# MainControl20V05.net
KiCad netlist of a schematic drawn in Altium Designer
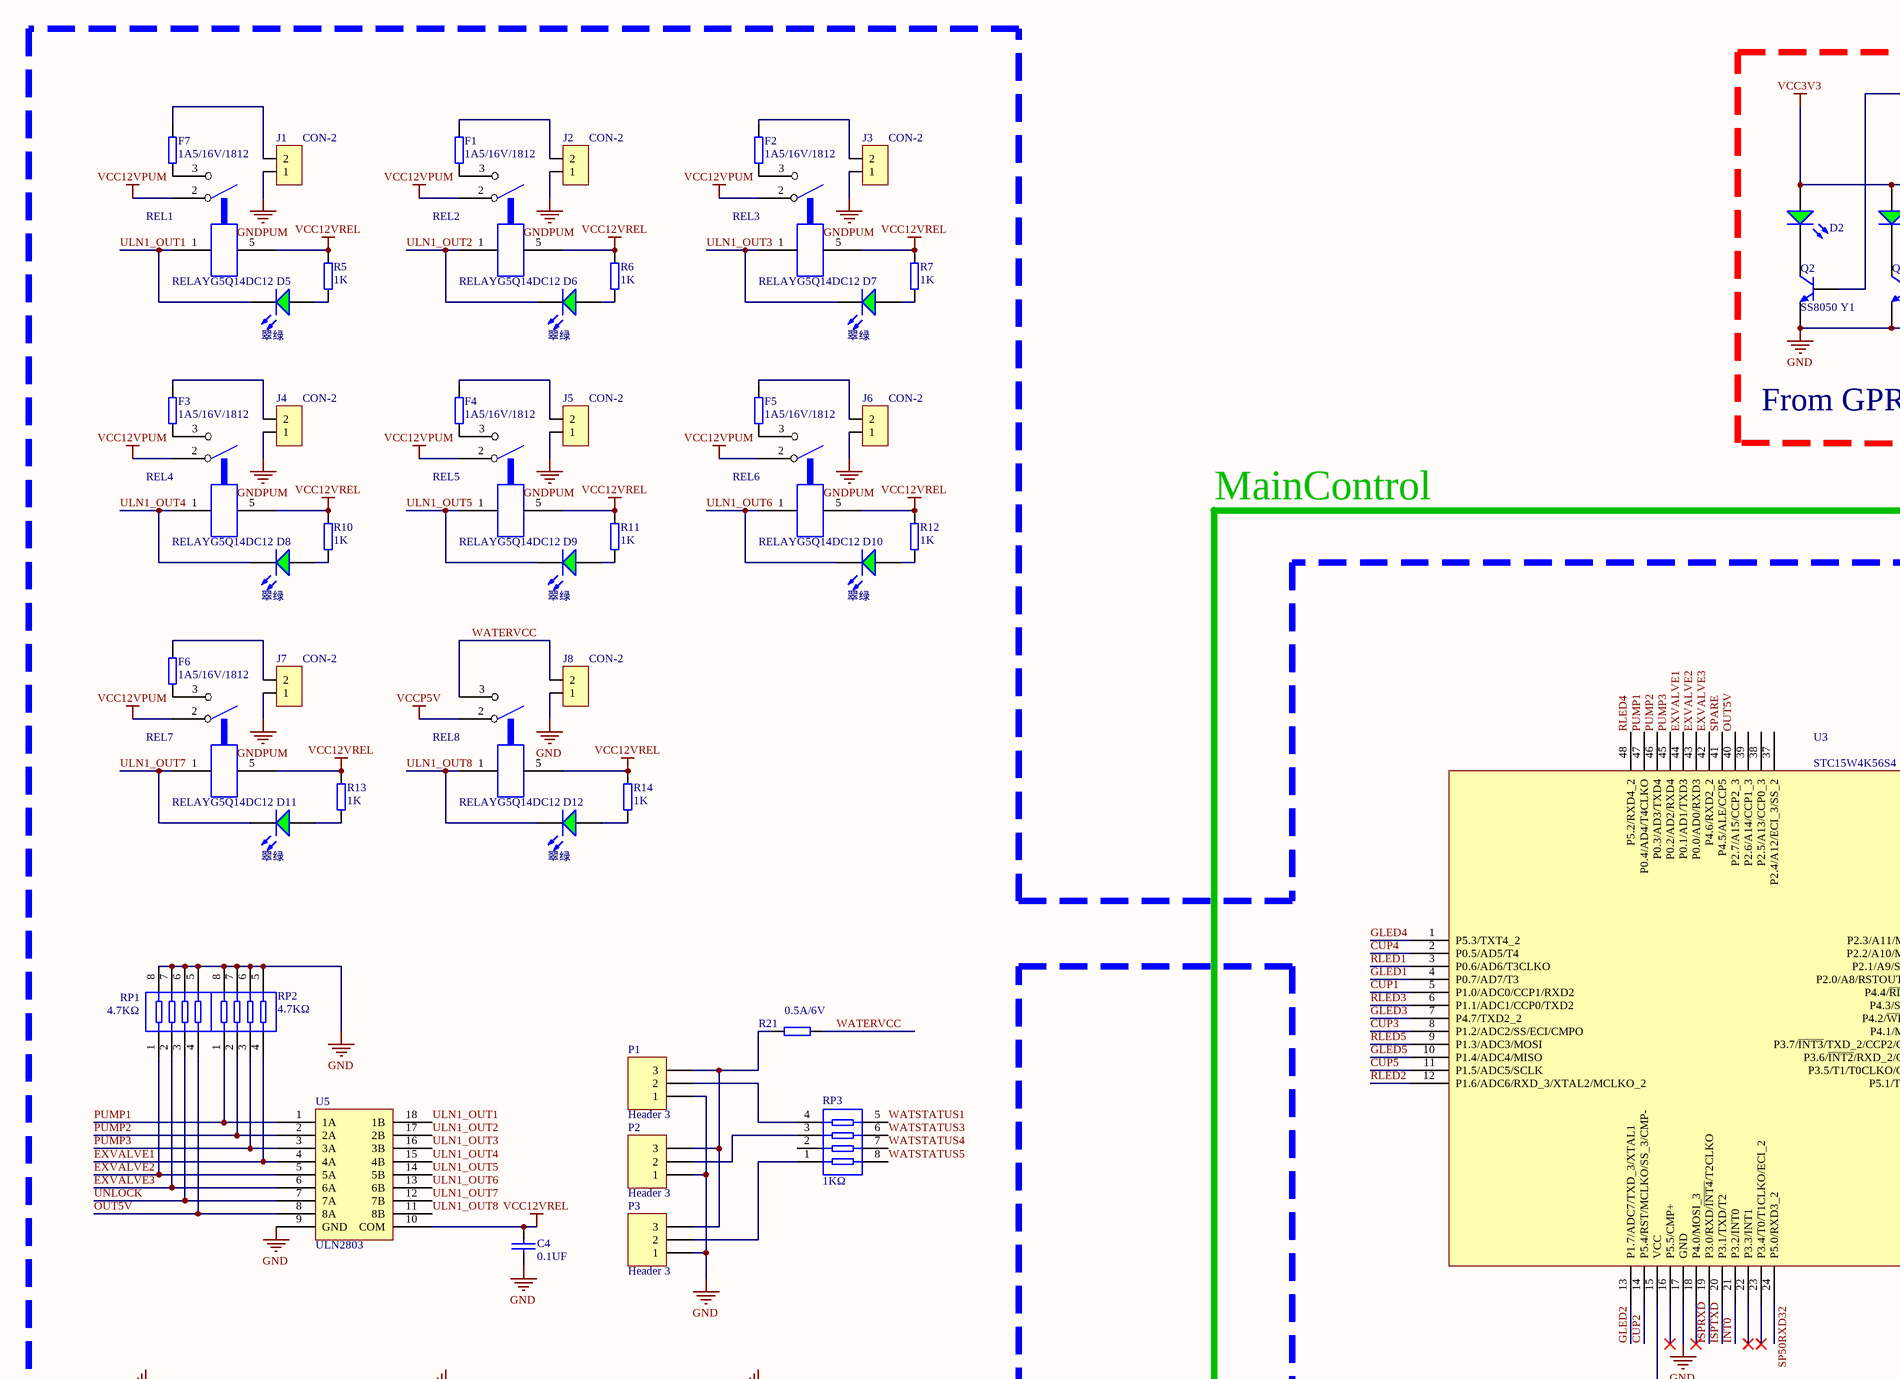
[diagram p0: MainControl20V05.SchDoc, top left]
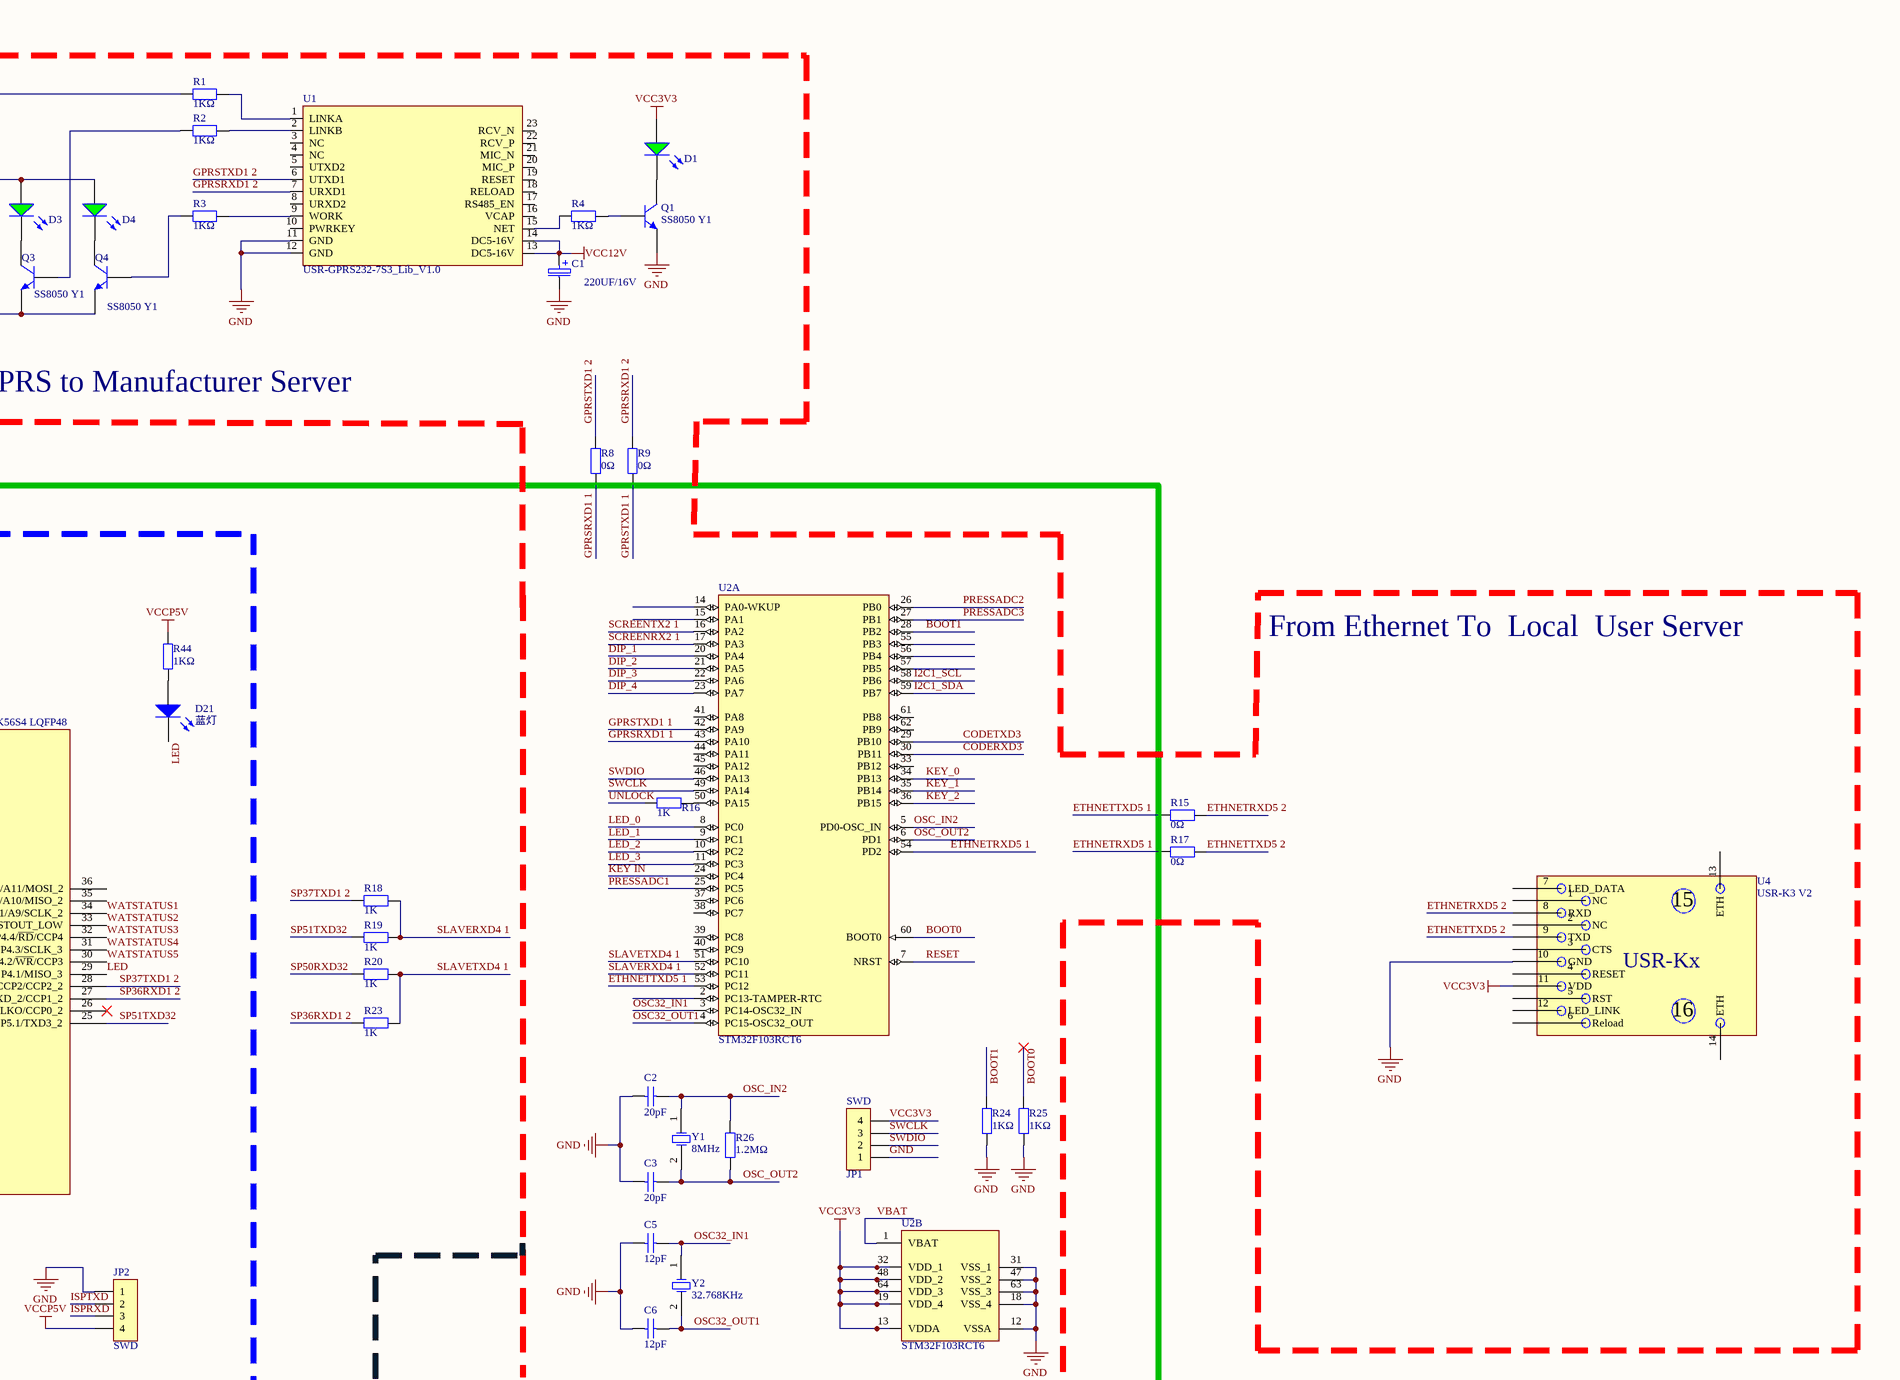
[diagram p1: MainControl20V05.SchDoc, top right]
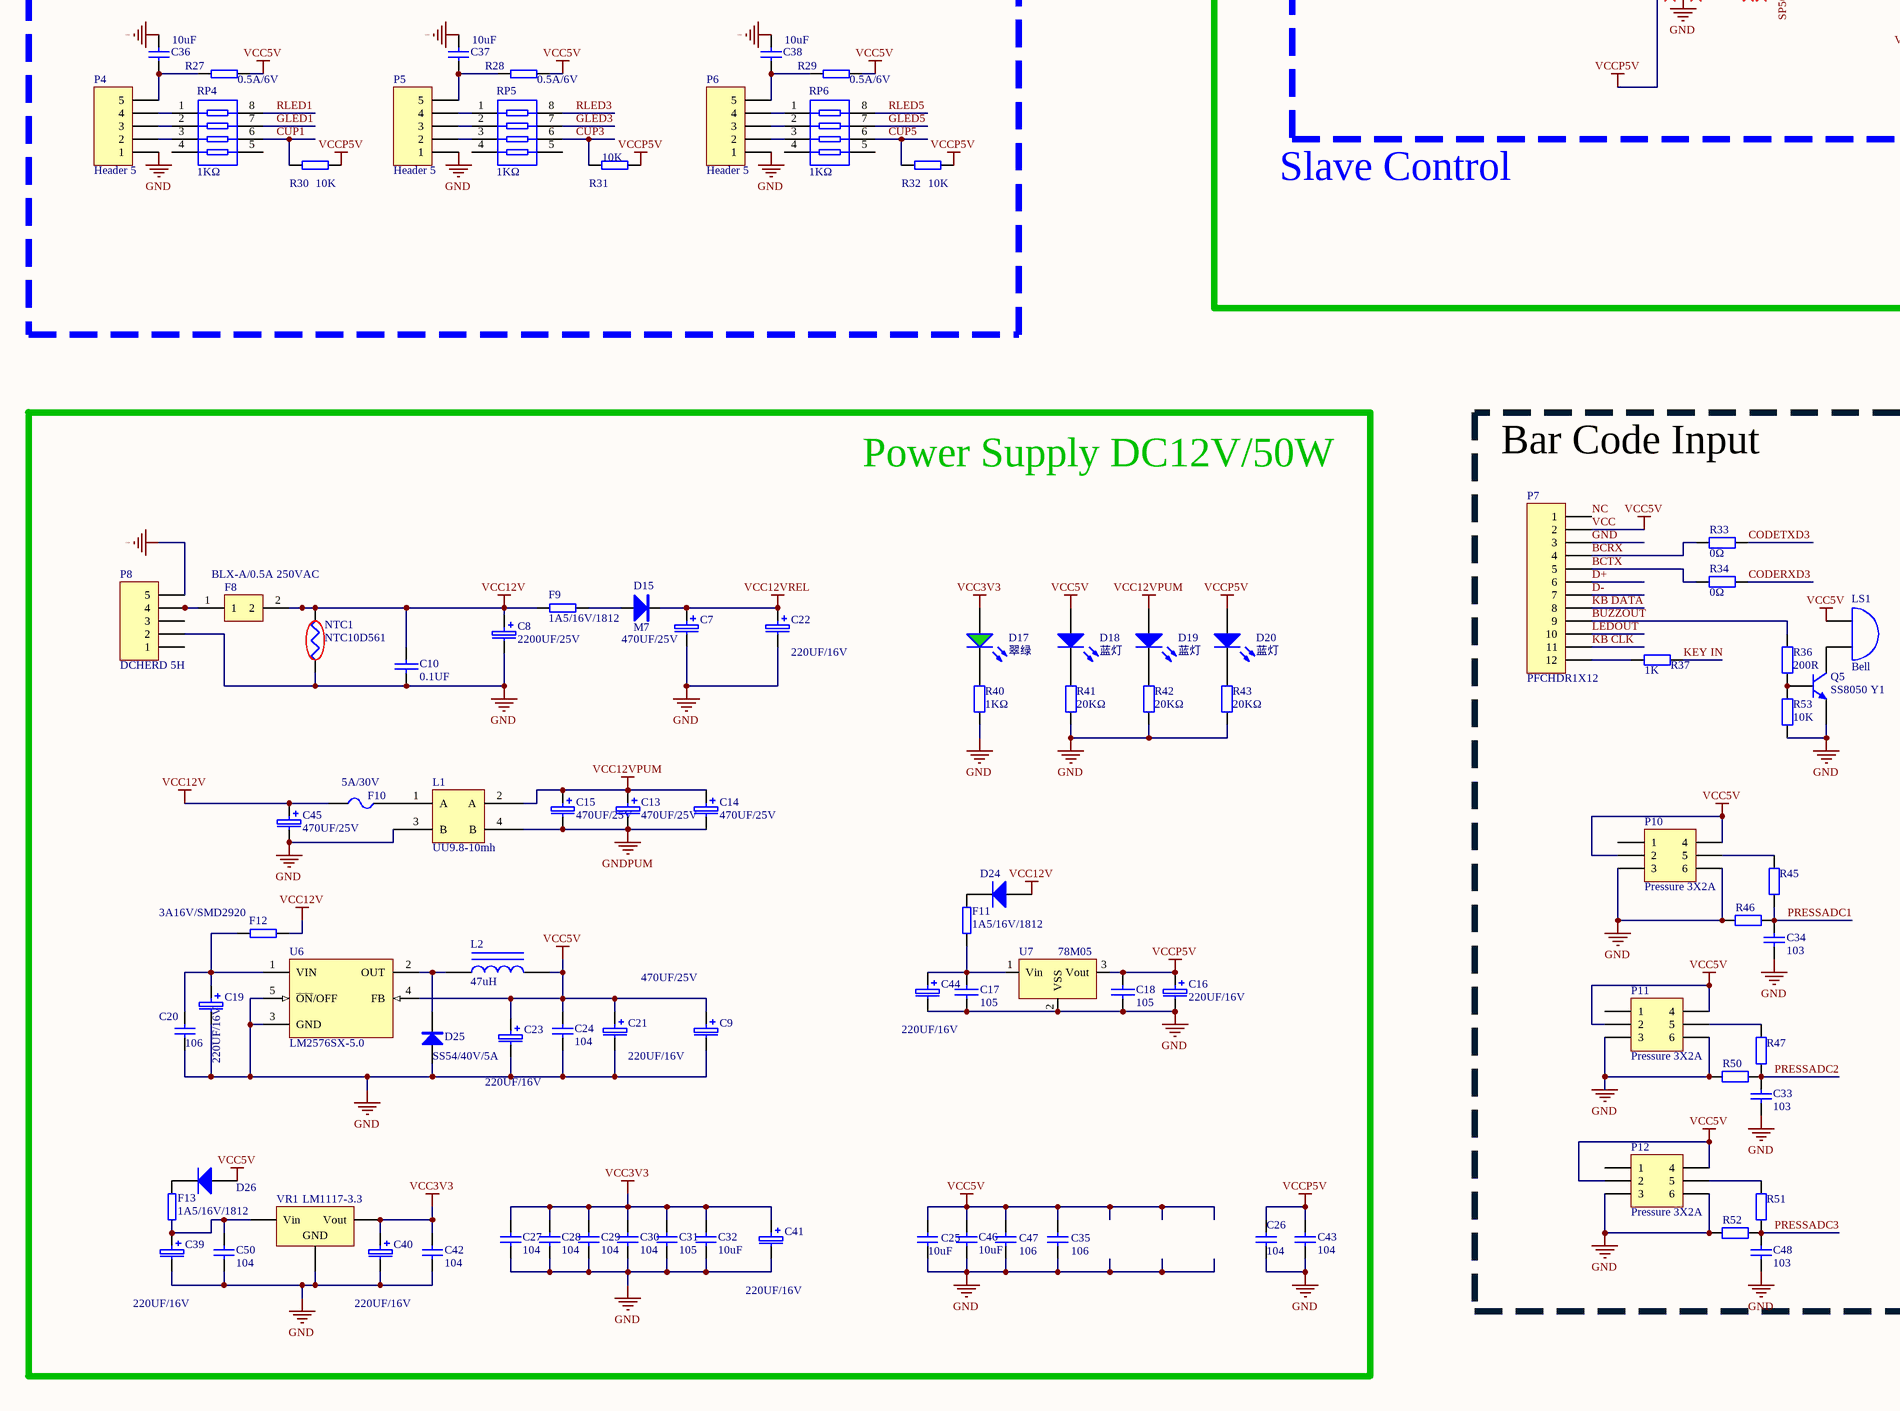
[diagram p2: MainControl20V05.SchDoc, bottom left]
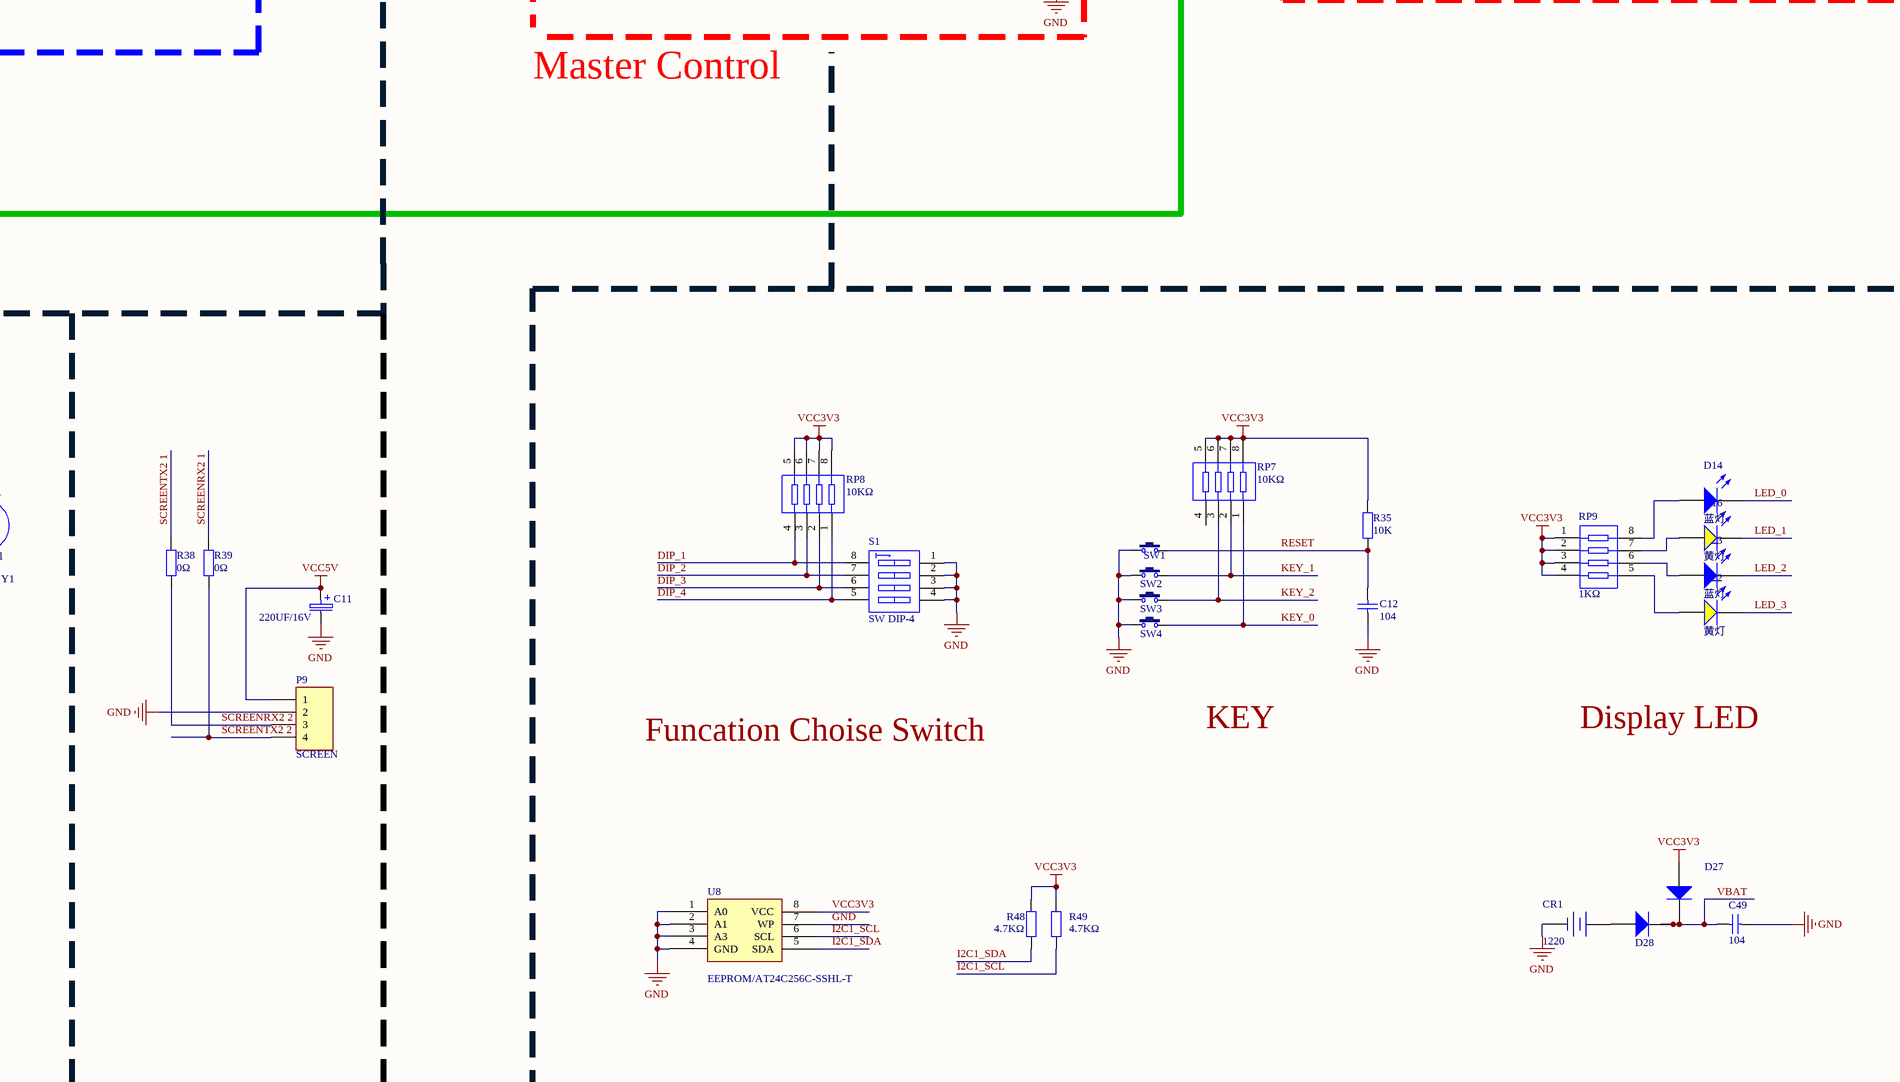
[diagram p3: MainControl20V05.SchDoc, bottom right]

(export (version "E")
  (design (tool "Eeschema 10.0.6"))
  (components
    (comp (ref "C1")
      (value "220UF/16V")
      (footprint "6SMD-ECAP-6.3X7.7")
      (libsource (lib "WegeV1") (part "EC"))
    )
    (comp (ref "C2")
      (value "20pF")
      (footprint "0805_C")
      (description "贴片电容")
      (libsource (lib "Cap") (part "1206 470pF (471) 10% 50V"))
    )
    (comp (ref "C3")
      (value "20pF")
      (footprint "0805_C")
      (description "贴片电容")
      (libsource (lib "Cap") (part "1206 470pF (471) 10% 50V"))
    )
    (comp (ref "C4")
      (value "0.1UF")
      (footprint "0805_C")
      (description "Cap")
      (libsource (lib "RX9910") (part "CAP-SMD"))
    )
    (comp (ref "C5")
      (value "12pF")
      (footprint "0805_C")
      (description "贴片电容")
      (libsource (lib "Cap") (part "1206 470pF (471) 10% 50V"))
    )
    (comp (ref "C6")
      (value "12pF")
      (footprint "0805_C")
      (description "贴片电容")
      (libsource (lib "Cap") (part "1206 470pF (471) 10% 50V"))
    )
    (comp (ref "C7") (value "470UF/25V") (footprint "C1020") (libsource (lib "WegeV1") (part "EC")))
    (comp (ref "C8") (value "2200UF/25V") (footprint "C3618") (libsource (lib "WegeV1") (part "EC")))
    (comp (ref "C9") (value "470UF/25V") (footprint "C1020") (libsource (lib "WegeV1") (part "EC")))
    (comp (ref "C10")
      (value "0.1UF")
      (footprint "0805_C")
      (description "安规电容 X2 275V 0.1uF 100nF 104K 脚距10mm")
      (libsource (lib "WegeV1") (part "CAP-X"))
    )
    (comp (ref "C11")
      (value "220UF/16V")
      (footprint "6SMD-ECAP-6.3X7.7")
      (libsource (lib "WegeV1") (part "EC"))
    )
    (comp (ref "C12")
      (value "104")
      (footprint "0805_C")
      (description "贴片电容")
      (libsource (lib "Cap") (part "1206 100nF (104) 10% 50V"))
    )
    (comp (ref "C13") (value "470UF/25V") (footprint "C1020") (libsource (lib "WegeV1") (part "EC")))
    (comp (ref "C14") (value "470UF/25V") (footprint "C1020") (libsource (lib "WegeV1") (part "EC")))
    (comp (ref "C15") (value "470UF/25V") (footprint "C1020") (libsource (lib "WegeV1") (part "EC")))
    (comp (ref "C16")
      (value "220UF/16V")
      (footprint "6SMD-ECAP-6.3X7.7")
      (libsource (lib "WegeV1") (part "EC"))
    )
    (comp (ref "C17")
      (value "105")
      (footprint "0805_C")
      (description "Cap")
      (libsource (lib "RX9910") (part "CAP-SMD"))
    )
    (comp (ref "C18")
      (value "105")
      (footprint "0805_C")
      (description "Cap")
      (libsource (lib "RX9910") (part "CAP-SMD"))
    )
    (comp (ref "C19")
      (value "220UF/16V")
      (footprint "6SMD-ECAP-6.3X7.7")
      (libsource (lib "WegeV1") (part "EC"))
    )
    (comp (ref "C20")
      (value "106")
      (footprint "1206_R")
      (description "贴片电容")
      (libsource (lib "Cap") (part "1206 10uF (106) 10% 50V"))
    )
    (comp (ref "C21")
      (value "220UF/16V")
      (footprint "6SMD-ECAP-6.3X7.7")
      (libsource (lib "WegeV1") (part "EC"))
    )
    (comp (ref "C22")
      (value "220UF/16V")
      (footprint "6SMD-ECAP-6.3X7.7")
      (libsource (lib "WegeV1") (part "EC"))
    )
    (comp (ref "C23")
      (value "220UF/16V")
      (footprint "6SMD-ECAP-6.3X7.7")
      (libsource (lib "WegeV1") (part "EC"))
    )
    (comp (ref "C24")
      (value "104")
      (footprint "0805_C")
      (description "贴片电容")
      (libsource (lib "Cap") (part "1206 220nF (224) 10% 50V"))
    )
    (comp (ref "C25")
      (value "10uF")
      (footprint "0805_C")
      (description "贴片电容")
      (libsource (lib "Cap") (part "1206 100nF (104) 10% 50V"))
    )
    (comp (ref "C26")
      (value "104")
      (footprint "0805_C")
      (description "贴片电容")
      (libsource (lib "Cap") (part "1206 100nF (104) 10% 50V"))
    )
    (comp (ref "C27")
      (value "104")
      (footprint "0805_C")
      (description "贴片电容")
      (libsource (lib "Cap") (part "1206 100nF (104) 10% 50V"))
    )
    (comp (ref "C28")
      (value "104")
      (footprint "0805_C")
      (description "贴片电容")
      (libsource (lib "Cap") (part "1206 100nF (104) 10% 50V"))
    )
    (comp (ref "C29")
      (value "104")
      (footprint "0805_C")
      (description "贴片电容")
      (libsource (lib "Cap") (part "1206 100nF (104) 10% 50V"))
    )
    (comp (ref "C30")
      (value "104")
      (footprint "0805_C")
      (description "贴片电容")
      (libsource (lib "Cap") (part "1206 100nF (104) 10% 50V"))
    )
    (comp (ref "C31")
      (value "105")
      (footprint "0805_C")
      (description "贴片电容")
      (libsource (lib "Cap") (part "1206 100nF (104) 10% 50V"))
    )
    (comp (ref "C32")
      (value "10uF")
      (footprint "0805_C")
      (description "贴片电容")
      (libsource (lib "Cap") (part "1206 100nF (104) 10% 50V"))
    )
    (comp (ref "C33")
      (value "103")
      (footprint "0805_C")
      (description "贴片电容")
      (libsource (lib "Cap") (part "1206 100nF (104) 10% 50V"))
    )
    (comp (ref "C34")
      (value "103")
      (footprint "0805_C")
      (description "贴片电容")
      (libsource (lib "Cap") (part "1206 100nF (104) 10% 50V"))
    )
    (comp (ref "C35")
      (value "106")
      (footprint "0805_C")
      (description "贴片电容")
      (libsource (lib "Cap") (part "1206 10uF (106) 10% 50V"))
    )
    (comp (ref "C36")
      (value "10uF")
      (footprint "0805_C")
      (description "贴片电容")
      (libsource (lib "Cap") (part "1206 100nF (104) 10% 50V"))
    )
    (comp (ref "C37")
      (value "10uF")
      (footprint "0805_C")
      (description "贴片电容")
      (libsource (lib "Cap") (part "1206 100nF (104) 10% 50V"))
    )
    (comp (ref "C38")
      (value "10uF")
      (footprint "0805_C")
      (description "贴片电容")
      (libsource (lib "Cap") (part "1206 100nF (104) 10% 50V"))
    )
    (comp (ref "C39")
      (value "220UF/16V")
      (footprint "6SMD-ECAP-6.3X7.7")
      (libsource (lib "WegeV1") (part "EC"))
    )
    (comp (ref "C40")
      (value "220UF/16V")
      (footprint "6SMD-ECAP-6.3X7.7")
      (libsource (lib "WegeV1") (part "EC"))
    )
    (comp (ref "C41")
      (value "220UF/16V")
      (footprint "6SMD-ECAP-6.3X7.7")
      (libsource (lib "WegeV1") (part "EC"))
    )
    (comp (ref "C42")
      (value "104")
      (footprint "0805_C")
      (description "贴片电容")
      (libsource (lib "Cap") (part "1206 100nF (104) 10% 50V"))
    )
    (comp (ref "C43")
      (value "104")
      (footprint "0805_C")
      (description "贴片电容")
      (libsource (lib "Cap") (part "1206 100nF (104) 10% 50V"))
    )
    (comp (ref "C44")
      (value "220UF/16V")
      (footprint "6SMD-ECAP-6.3X7.7")
      (libsource (lib "WegeV1") (part "EC"))
    )
    (comp (ref "C45") (value "470UF/25V") (footprint "C1020") (libsource (lib "WegeV1") (part "EC")))
    (comp (ref "C46")
      (value "10uF")
      (footprint "0805_C")
      (description "贴片电容")
      (libsource (lib "Cap") (part "1206 100nF (104) 10% 50V"))
    )
    (comp (ref "C47")
      (value "106")
      (description "贴片电容")
      (libsource (lib "Cap") (part "1206 10uF (106) 10% 50V"))
    )
    (comp (ref "C48")
      (value "103")
      (footprint "0805_C")
      (description "贴片电容")
      (libsource (lib "Cap") (part "1206 100nF (104) 10% 50V"))
    )
    (comp (ref "C49")
      (value "104")
      (footprint "0805_C")
      (description "贴片电容")
      (libsource (lib "Cap") (part "1206 100nF (104) 10% 50V"))
    )
    (comp (ref "C50")
      (value "104")
      (footprint "0805_C")
      (description "贴片电容")
      (libsource (lib "Cap") (part "1206 100nF (104) 10% 50V"))
    )
    (comp (ref "CR1")
      (value "1220")
      (footprint "CR1220_A")
      (description "微型电池")
      (fields (field (name "版权归属") "源创客"))
      (libsource (lib "15.1 - 未分类器件") (part "CR-3V"))
    )
    (comp (ref "D1")
      (value "翠绿")
      (footprint "0805_LED_S1")
      (description "发光二极管")
      (libsource (lib "LED") (part "0805 翠绿"))
    )
    (comp (ref "D2")
      (value "翠绿")
      (footprint "0805_LED_S1")
      (description "发光二极管")
      (libsource (lib "LED") (part "0805 翠绿"))
    )
    (comp (ref "D3")
      (value "翠绿")
      (footprint "0805_LED_S1")
      (description "发光二极管")
      (libsource (lib "LED") (part "0805 翠绿"))
    )
    (comp (ref "D4")
      (value "翠绿")
      (footprint "0805_LED_S1")
      (description "发光二极管")
      (libsource (lib "LED") (part "0805 翠绿"))
    )
    (comp (ref "D5")
      (value "翠绿")
      (footprint "0805_LED_S1")
      (description "发光二极管")
      (libsource (lib "LED") (part "0805 翠绿"))
    )
    (comp (ref "D6")
      (value "翠绿")
      (footprint "0805_LED_S1")
      (description "发光二极管")
      (libsource (lib "LED") (part "0805 翠绿"))
    )
    (comp (ref "D7")
      (value "翠绿")
      (footprint "0805_LED_S1")
      (description "发光二极管")
      (libsource (lib "LED") (part "0805 翠绿"))
    )
    (comp (ref "D8")
      (value "翠绿")
      (footprint "0805_LED_S1")
      (description "发光二极管")
      (libsource (lib "LED") (part "0805 翠绿"))
    )
    (comp (ref "D9")
      (value "翠绿")
      (footprint "0805_LED_S1")
      (description "发光二极管")
      (libsource (lib "LED") (part "0805 翠绿"))
    )
    (comp (ref "D10")
      (value "翠绿")
      (footprint "0805_LED_S1")
      (description "发光二极管")
      (libsource (lib "LED") (part "0805 翠绿"))
    )
    (comp (ref "D11")
      (value "翠绿")
      (footprint "0805_LED_S1")
      (description "发光二极管")
      (libsource (lib "LED") (part "0805 翠绿"))
    )
    (comp (ref "D12")
      (value "翠绿")
      (footprint "0805_LED_S1")
      (description "发光二极管")
      (libsource (lib "LED") (part "0805 翠绿"))
    )
    (comp (ref "D14")
      (value "蓝灯")
      (footprint "0805_LED_S1")
      (description "发光二极管")
      (libsource (lib "LED") (part "0805 蓝灯"))
    )
    (comp (ref "D15") (value "M7") (footprint "DO-41") (libsource (lib "WegeV1") (part "M7")))
    (comp (ref "D16")
      (value "黄灯")
      (footprint "0805_LED_S1")
      (description "发光二极管")
      (libsource (lib "LED") (part "0805 黄灯"))
    )
    (comp (ref "D17")
      (value "翠绿")
      (footprint "0805_LED_S1")
      (description "发光二极管")
      (libsource (lib "LED") (part "0805 翠绿"))
    )
    (comp (ref "D18")
      (value "蓝灯")
      (footprint "0805_LED_S1")
      (description "发光二极管")
      (libsource (lib "LED") (part "0805 蓝灯"))
    )
    (comp (ref "D19")
      (value "蓝灯")
      (footprint "0805_LED_S1")
      (description "发光二极管")
      (libsource (lib "LED") (part "0805 蓝灯"))
    )
    (comp (ref "D20")
      (value "蓝灯")
      (footprint "0805_LED_S1")
      (description "发光二极管")
      (libsource (lib "LED") (part "0805 蓝灯"))
    )
    (comp (ref "D21")
      (value "蓝灯")
      (footprint "0805_LED_S1")
      (description "发光二极管")
      (libsource (lib "LED") (part "0805 蓝灯"))
    )
    (comp (ref "D22")
      (value "黄灯")
      (footprint "0805_LED_S1")
      (description "发光二极管")
      (libsource (lib "LED") (part "0805 黄灯"))
    )
    (comp (ref "D23")
      (value "蓝灯")
      (footprint "0805_LED_S1")
      (description "发光二极管")
      (libsource (lib "LED") (part "0805 蓝灯"))
    )
    (comp (ref "D24")
      (value "LL4148 LL-34 1206")
      (footprint "LL-34")
      (description "开关二极管")
      (libsource (lib "Diode") (part "LL-34 LL4148 LL-34 1206"))
    )
    (comp (ref "D25")
      (value "SS54/40V/5A")
      (footprint "SMC(DO-214AB)_S1")
      (description "肖特基二极管")
      (fields (field (name "版权归属") "源创客"))
      (libsource (lib "8.1   - 二极管-整流桥") (part "1N5819"))
    )
    (comp (ref "D26")
      (value "LL4148 LL-34 1206")
      (footprint "LL-34")
      (description "开关二极管")
      (libsource (lib "Diode") (part "LL-34 LL4148 LL-34 1206"))
    )
    (comp (ref "D27")
      (value "LL4148 LL-34 1206")
      (footprint "LL-34")
      (description "开关二极管")
      (libsource (lib "Diode") (part "LL-34 LL4148 LL-34 1206"))
    )
    (comp (ref "D28")
      (value "LL4148 LL-34 1206")
      (footprint "LL-34")
      (description "开关二极管")
      (libsource (lib "Diode") (part "LL-34 LL4148 LL-34 1206"))
    )
    (comp (ref "F1")
      (value "1A5/16V/1812")
      (footprint "1812_R")
      (description "SMD")
      (libsource (lib "RX9910") (part "RES-SMD"))
    )
    (comp (ref "F2")
      (value "1A5/16V/1812")
      (footprint "1812_R")
      (description "SMD")
      (libsource (lib "RX9910") (part "RES-SMD"))
    )
    (comp (ref "F3")
      (value "1A5/16V/1812")
      (footprint "1812_R")
      (description "SMD")
      (libsource (lib "RX9910") (part "RES-SMD"))
    )
    (comp (ref "F4")
      (value "1A5/16V/1812")
      (footprint "1812_R")
      (description "SMD")
      (libsource (lib "RX9910") (part "RES-SMD"))
    )
    (comp (ref "F5")
      (value "1A5/16V/1812")
      (footprint "1812_R")
      (description "SMD")
      (libsource (lib "RX9910") (part "RES-SMD"))
    )
    (comp (ref "F6")
      (value "1A5/16V/1812")
      (footprint "1812_R")
      (description "SMD")
      (libsource (lib "RX9910") (part "RES-SMD"))
    )
    (comp (ref "F7")
      (value "1A5/16V/1812")
      (footprint "1812_R")
      (description "SMD")
      (libsource (lib "RX9910") (part "RES-SMD"))
    )
    (comp (ref "F8")
      (value "BLX-A/0.5A 250VAC")
      (footprint "RL30-500")
      (libsource (lib "WegeV1") (part "BLX-A"))
    )
    (comp (ref "F9")
      (value "1A5/16V/1812")
      (footprint "1812_R")
      (description "SMD")
      (libsource (lib "RX9910") (part "RES-SMD"))
    )
    (comp (ref "F10")
      (value "5A/30V")
      (footprint "RL30-500")
      (description "贴片保险丝")
      (fields (field (name "版权归属") "源创客"))
      (libsource (lib "10.1 - 保险丝-晶振") (part "FU"))
    )
    (comp (ref "F11")
      (value "1A5/16V/1812")
      (footprint "1812_R")
      (description "SMD")
      (libsource (lib "RX9910") (part "RES-SMD"))
    )
    (comp (ref "F12")
      (value "3A16V/SMD2920")
      (footprint "SMD2920")
      (description "SMD")
      (libsource (lib "RX9910") (part "RES-SMD"))
    )
    (comp (ref "F13")
      (value "1A5/16V/1812")
      (footprint "1812_R")
      (description "SMD")
      (libsource (lib "RX9910") (part "RES-SMD"))
    )
    (comp (ref "J1") (value "CON-2") (footprint "F396P2-1") (libsource (lib "WegeV1") (part "CON-2")))
    (comp (ref "J2") (value "CON-2") (footprint "F396P2-1") (libsource (lib "WegeV1") (part "CON-2")))
    (comp (ref "J3") (value "CON-2") (footprint "F396P2-1") (libsource (lib "WegeV1") (part "CON-2")))
    (comp (ref "J4") (value "CON-2") (footprint "F396P2-1") (libsource (lib "WegeV1") (part "CON-2")))
    (comp (ref "J5") (value "CON-2") (footprint "F396P2-1") (libsource (lib "WegeV1") (part "CON-2")))
    (comp (ref "J6") (value "CON-2") (footprint "F396P2-1") (libsource (lib "WegeV1") (part "CON-2")))
    (comp (ref "J7") (value "CON-2") (footprint "F396P2-1") (libsource (lib "WegeV1") (part "CON-2")))
    (comp (ref "J8") (value "CON-2") (footprint "F396P2-1") (libsource (lib "WegeV1") (part "CON-2")))
    (comp (ref "JP1")
      (value "SWD")
      (footprint "HDR2.54-M-LI-4P")
      (description "4P接插件")
      (fields (field (name "版权归属") "源创客"))
      (libsource (lib "") (part "Header 4_1"))
    )
    (comp (ref "JP2")
      (value "SWD")
      (footprint "HDR2.54-M-LI-4P")
      (description "4P接插件")
      (fields (field (name "版权归属") "源创客"))
      (libsource (lib "4.5   - 接插件-脚距2.54") (part "Header 4"))
    )
    (comp (ref "L1") (value "UU9.8-10mh") (footprint "TRANS") (libsource (lib "WegeV1") (part "INL-9.8MM")))
    (comp (ref "L2")
      (value "47uH")
      (footprint "H4.7UH")
      (description "贴片电感")
      (libsource (lib "IUD") (part "1206 10uH 10%"))
    )
    (comp (ref "LS1")
      (value "Bell")
      (footprint "BUZZ")
      (description "Electrical Bell")
      (fields (field (name "PUBLISHER") "Altium Limited"))
      (libsource (lib "Miscellaneous Devices") (part "Bell"))
    )
    (comp (ref "NTC1") (value "NTC10D561") (footprint "NTC-10D") (libsource (lib "WegeV1") (part "NTC")))
    (comp (ref "P1")
      (value "Header 3")
      (footprint "XHB3")
      (description "Header, 3-Pin")
      (fields (field (name "PUBLISHER") "Altium Limited"))
      (libsource (lib "Miscellaneous Connectors") (part "Header 3"))
    )
    (comp (ref "P2")
      (value "Header 3")
      (footprint "XHB3")
      (description "Header, 3-Pin")
      (fields (field (name "PUBLISHER") "Altium Limited"))
      (libsource (lib "Miscellaneous Connectors") (part "Header 3"))
    )
    (comp (ref "P3")
      (value "Header 3")
      (footprint "XHB3")
      (description "Header, 3-Pin")
      (fields (field (name "PUBLISHER") "Altium Limited"))
      (libsource (lib "Miscellaneous Connectors") (part "Header 3"))
    )
    (comp (ref "P4")
      (value "Header 5")
      (footprint "XHB5")
      (description "Header, 5-Pin")
      (fields (field (name "PUBLISHER") "Altium Limited"))
      (libsource (lib "Miscellaneous Connectors") (part "Header 5"))
    )
    (comp (ref "P5")
      (value "Header 5")
      (footprint "XHB5")
      (description "Header, 5-Pin")
      (fields (field (name "PUBLISHER") "Altium Limited"))
      (libsource (lib "Miscellaneous Connectors") (part "Header 5"))
    )
    (comp (ref "P6")
      (value "Header 5")
      (footprint "XHB5")
      (description "Header, 5-Pin")
      (fields (field (name "PUBLISHER") "Altium Limited"))
      (libsource (lib "Miscellaneous Connectors") (part "Header 5"))
    )
    (comp (ref "P7")
      (value "PFCHDR1X12")
      (footprint "FPC12/0.5")
      (description "Header, 12-Pin")
      (fields (field (name "PUBLISHER") "Altium Limited"))
      (libsource (lib "Miscellaneous Connectors") (part "MHDR1X12"))
    )
    (comp (ref "P8")
      (value "DCHERD 5H")
      (footprint "DCCON")
      (description "Header, 5-Pin, Right Angle")
      (fields (field (name "PUBLISHER") "Altium Limited"))
      (libsource (lib "Miscellaneous Connectors") (part "Header 5H"))
    )
    (comp (ref "P9")
      (value "SCREEN")
      (footprint "MHDR1X4")
      (description "Header, 4-Pin")
      (fields (field (name "PUBLISHER") "Altium Limited"))
      (libsource (lib "Miscellaneous Connectors") (part "MHDR1X4"))
    )
    (comp (ref "P10")
      (value "Pressure 3X2A")
      (footprint "PRESS")
      (description "Header, 3-Pin, Dual row")
      (fields (field (name "PUBLISHER") "Altium Limited"))
      (libsource (lib "Miscellaneous Connectors") (part "Header 3X2A"))
    )
    (comp (ref "P11")
      (value "Pressure 3X2A")
      (footprint "PRESS")
      (description "Header, 3-Pin, Dual row")
      (fields (field (name "PUBLISHER") "Altium Limited"))
      (libsource (lib "Miscellaneous Connectors") (part "Header 3X2A"))
    )
    (comp (ref "P12")
      (value "Pressure 3X2A")
      (footprint "PRESS")
      (description "Header, 3-Pin, Dual row")
      (fields (field (name "PUBLISHER") "Altium Limited"))
      (libsource (lib "Miscellaneous Connectors") (part "Header 3X2A"))
    )
    (comp (ref "Q1")
      (value "SS8050 Y1")
      (footprint "SOT-23(SOT-23-3)")
      (description "三极管")
      (libsource (lib "Transistor_NPN") (part "SOT-23 SS8050 Y1"))
    )
    (comp (ref "Q2")
      (value "SS8050 Y1")
      (footprint "SOT-23(SOT-23-3)")
      (description "三极管")
      (libsource (lib "Transistor_NPN") (part "SOT-23 SS8050 Y1"))
    )
    (comp (ref "Q3")
      (value "SS8050 Y1")
      (footprint "SOT-23(SOT-23-3)")
      (description "三极管")
      (libsource (lib "Transistor_NPN") (part "SOT-23 SS8050 Y1"))
    )
    (comp (ref "Q4")
      (value "SS8050 Y1")
      (footprint "SOT-23(SOT-23-3)")
      (description "三极管")
      (libsource (lib "Transistor_NPN") (part "SOT-23 SS8050 Y1"))
    )
    (comp (ref "Q5")
      (value "SS8050 Y1")
      (footprint "SOT-23(SOT-23-3)")
      (description "三极管")
      (libsource (lib "Transistor_NPN") (part "SOT-23 SS8050 Y1"))
    )
    (comp (ref "R1")
      (value "1KΩ")
      (footprint "0805_R")
      (description "贴片电阻")
      (libsource (lib "") (part "1206 1KΩ (1001) 1%_2"))
    )
    (comp (ref "R2")
      (value "1KΩ")
      (footprint "0805_R")
      (description "贴片电阻")
      (libsource (lib "") (part "1206 1KΩ (1001) 1%_2"))
    )
    (comp (ref "R3")
      (value "1KΩ")
      (footprint "0805_R")
      (description "贴片电阻")
      (libsource (lib "") (part "1206 1KΩ (1001) 1%_2"))
    )
    (comp (ref "R4")
      (value "1KΩ")
      (footprint "0805_R")
      (description "贴片电阻")
      (libsource (lib "") (part "1206 1KΩ (1001) 1%_3"))
    )
    (comp (ref "R5") (value "1K") (footprint "0805_R") (libsource (lib "WegeV1") (part "RES")))
    (comp (ref "R6") (value "1K") (footprint "0805_R") (libsource (lib "WegeV1") (part "RES")))
    (comp (ref "R7") (value "1K") (footprint "0805_R") (libsource (lib "WegeV1") (part "RES")))
    (comp (ref "R8")
      (value "0Ω")
      (footprint "0805_R")
      (description "贴片电阻")
      (libsource (lib "") (part "1206 0Ω (0R0) 1%_1"))
    )
    (comp (ref "R9")
      (value "0Ω")
      (footprint "0805_R")
      (description "贴片电阻")
      (libsource (lib "") (part "1206 0Ω (0R0) 1%_1"))
    )
    (comp (ref "R10") (value "1K") (footprint "0805_R") (libsource (lib "WegeV1") (part "RES")))
    (comp (ref "R11") (value "1K") (footprint "0805_R") (libsource (lib "WegeV1") (part "RES")))
    (comp (ref "R12") (value "1K") (footprint "0805_R") (libsource (lib "WegeV1") (part "RES")))
    (comp (ref "R13") (value "1K") (footprint "0805_R") (libsource (lib "WegeV1") (part "RES")))
    (comp (ref "R14") (value "1K") (footprint "0805_R") (libsource (lib "WegeV1") (part "RES")))
    (comp (ref "R15")
      (value "0Ω")
      (footprint "0805_R")
      (description "贴片电阻")
      (libsource (lib "RES") (part "1206 0Ω (0R0) 1%"))
    )
    (comp (ref "R16")
      (value "1K")
      (footprint "0805_R")
      (description "贴片电阻")
      (libsource (lib "RES") (part "1206 0Ω (0R0) 1%"))
    )
    (comp (ref "R17")
      (value "0Ω")
      (footprint "0805_R")
      (description "贴片电阻")
      (libsource (lib "RES") (part "1206 0Ω (0R0) 1%"))
    )
    (comp (ref "R18")
      (value "1K")
      (footprint "0805_R")
      (description "贴片电阻")
      (libsource (lib "RES") (part "1206 0Ω (0R0) 1%"))
    )
    (comp (ref "R19")
      (value "1K")
      (footprint "0805_R")
      (description "贴片电阻")
      (libsource (lib "RES") (part "1206 0Ω (0R0) 1%"))
    )
    (comp (ref "R20")
      (value "1K")
      (footprint "0805_R")
      (description "贴片电阻")
      (libsource (lib "RES") (part "1206 0Ω (0R0) 1%"))
    )
    (comp (ref "R21") (value "0.5A/6V") (footprint "1206_R") (libsource (lib "WegeV1") (part "RES")))
    (comp (ref "R23")
      (value "1K")
      (footprint "0805_R")
      (description "贴片电阻")
      (libsource (lib "RES") (part "1206 0Ω (0R0) 1%"))
    )
    (comp (ref "R24")
      (value "1KΩ")
      (footprint "0805_R")
      (description "贴片电阻")
      (libsource (lib "") (part "1206 1KΩ (1001) 1%_1"))
    )
    (comp (ref "R25")
      (value "1KΩ")
      (footprint "0805_R")
      (description "贴片电阻")
      (libsource (lib "") (part "1206 1KΩ (1001) 1%_1"))
    )
    (comp (ref "R26")
      (value "1.2MΩ")
      (footprint "0805_R")
      (description "贴片电阻")
      (libsource (lib "RES") (part "1206 1.2MΩ (1204) 1%"))
    )
    (comp (ref "R27") (value "0.5A/6V") (footprint "1206_R") (libsource (lib "WegeV1") (part "RES")))
    (comp (ref "R28") (value "0.5A/6V") (footprint "1206_R") (libsource (lib "WegeV1") (part "RES")))
    (comp (ref "R29") (value "0.5A/6V") (footprint "1206_R") (libsource (lib "WegeV1") (part "RES")))
    (comp (ref "R30") (value "10K") (footprint "0805_R") (libsource (lib "WegeV1") (part "RES")))
    (comp (ref "R31") (value "10K") (footprint "0805_R") (libsource (lib "WegeV1") (part "RES")))
    (comp (ref "R32") (value "10K") (footprint "0805_R") (libsource (lib "WegeV1") (part "RES")))
    (comp (ref "R33")
      (value "0Ω")
      (footprint "0805_R")
      (description "贴片电阻")
      (libsource (lib "RES") (part "1206 0Ω (0R0) 1%"))
    )
    (comp (ref "R34")
      (value "0Ω")
      (footprint "0805_R")
      (description "贴片电阻")
      (libsource (lib "RES") (part "1206 0Ω (0R0) 1%"))
    )
    (comp (ref "R35")
      (value "10K")
      (footprint "0805_R")
      (description "贴片电阻")
      (libsource (lib "") (part "1206 0Ω (0R0) 1%_1"))
    )
    (comp (ref "R36")
      (value "200R")
      (footprint "0805_R")
      (description "贴片电阻")
      (libsource (lib "") (part "1206 0Ω (0R0) 1%_1"))
    )
    (comp (ref "R37")
      (value "1K")
      (footprint "0805_R")
      (description "贴片电阻")
      (libsource (lib "RES") (part "1206 0Ω (0R0) 1%"))
    )
    (comp (ref "R38")
      (value "0Ω")
      (footprint "0805_R")
      (description "贴片电阻")
      (libsource (lib "") (part "1206 0Ω (0R0) 1%_1"))
    )
    (comp (ref "R39")
      (value "0Ω")
      (footprint "0805_R")
      (description "贴片电阻")
      (libsource (lib "") (part "1206 0Ω (0R0) 1%_1"))
    )
    (comp (ref "R40")
      (value "1KΩ")
      (footprint "0805_R")
      (description "贴片电阻")
      (libsource (lib "") (part "1206 1KΩ (1001) 1%_1"))
    )
    (comp (ref "R41")
      (value "20KΩ")
      (footprint "0805_R")
      (description "贴片电阻")
      (libsource (lib "RES") (part "1206 1KΩ (1001) 1%"))
    )
    (comp (ref "R42")
      (value "20KΩ")
      (footprint "0805_R")
      (description "贴片电阻")
      (libsource (lib "RES") (part "1206 1KΩ (1001) 1%"))
    )
    (comp (ref "R43")
      (value "20KΩ")
      (footprint "0805_R")
      (description "贴片电阻")
      (libsource (lib "RES") (part "1206 1KΩ (1001) 1%"))
    )
    (comp (ref "R44")
      (value "1KΩ")
      (footprint "0805_R")
      (description "贴片电阻")
      (libsource (lib "") (part "1206 1KΩ (1001) 1%_1"))
    )
    (comp (ref "R45")
      (value "68KΩ (6802) ±1%")
      (footprint "0805_R")
      (description "贴片电阻")
      (libsource (lib "RES") (part "0805 68KΩ (6802) 1%"))
    )
    (comp (ref "R46")
      (value "91KΩ (9102) ±1%")
      (footprint "0805_R")
      (description "贴片电阻")
      (libsource (lib "RES") (part "0805 91KΩ (9102) 1%"))
    )
    (comp (ref "R47")
      (value "68KΩ (6802) ±1%")
      (footprint "0805_R")
      (description "贴片电阻")
      (libsource (lib "RES") (part "0805 68KΩ (6802) 1%"))
    )
    (comp (ref "R48")
      (value "4.7KΩ")
      (footprint "0805_R")
      (description "贴片电阻")
      (libsource (lib "") (part "1206 1KΩ (1001) 1%_1"))
    )
    (comp (ref "R49")
      (value "4.7KΩ")
      (footprint "0805_R")
      (description "贴片电阻")
      (libsource (lib "") (part "1206 1KΩ (1001) 1%_1"))
    )
    (comp (ref "R50")
      (value "91KΩ (9102) ±1%")
      (footprint "0805_R")
      (description "贴片电阻")
      (libsource (lib "RES") (part "0805 91KΩ (9102) 1%"))
    )
    (comp (ref "R51")
      (value "68KΩ (6802) ±1%")
      (footprint "0805_R")
      (description "贴片电阻")
      (libsource (lib "RES") (part "0805 68KΩ (6802) 1%"))
    )
    (comp (ref "R52")
      (value "91KΩ (9102) ±1%")
      (footprint "0805_R")
      (description "贴片电阻")
      (libsource (lib "RES") (part "0805 91KΩ (9102) 1%"))
    )
    (comp (ref "R53")
      (value "10K")
      (footprint "0805_R")
      (description "贴片电阻")
      (libsource (lib "") (part "1206 0Ω (0R0) 1%_1"))
    )
    (comp (ref "REL1")
      (value "RELAYG5Q14DC12")
      (footprint "G5Q1")
      (libsource (lib "MainControl20V01") (part "RELAYG5Q14DC12"))
    )
    (comp (ref "REL2")
      (value "RELAYG5Q14DC12")
      (footprint "G5Q1")
      (libsource (lib "MainControl20V01") (part "RELAYG5Q14DC12"))
    )
    (comp (ref "REL3")
      (value "RELAYG5Q14DC12")
      (footprint "G5Q1")
      (libsource (lib "MainControl20V01") (part "RELAYG5Q14DC12"))
    )
    (comp (ref "REL4")
      (value "RELAYG5Q14DC12")
      (footprint "G5Q1")
      (libsource (lib "MainControl20V01") (part "RELAYG5Q14DC12"))
    )
    (comp (ref "REL5")
      (value "RELAYG5Q14DC12")
      (footprint "G5Q1")
      (libsource (lib "MainControl20V01") (part "RELAYG5Q14DC12"))
    )
    (comp (ref "REL6")
      (value "RELAYG5Q14DC12")
      (footprint "G5Q1")
      (libsource (lib "MainControl20V01") (part "RELAYG5Q14DC12"))
    )
    (comp (ref "REL7")
      (value "RELAYG5Q14DC12")
      (footprint "G5Q1")
      (libsource (lib "MainControl20V01") (part "RELAYG5Q14DC12"))
    )
    (comp (ref "REL8")
      (value "RELAYG5Q14DC12")
      (footprint "G5Q1")
      (libsource (lib "MainControl20V01") (part "RELAYG5Q14DC12"))
    )
    (comp (ref "RP1")
      (value "4.7KΩ")
      (footprint "0603_Rx4")
      (description "贴片排阻")
      (libsource (lib "RES") (part "0603*4  1KΩ (102) 5%"))
    )
    (comp (ref "RP2")
      (value "4.7KΩ")
      (footprint "0603_Rx4")
      (description "贴片排阻")
      (libsource (lib "RES") (part "0603*4  1KΩ (102) 5%"))
    )
    (comp (ref "RP3")
      (value "1KΩ")
      (footprint "0603_Rx4")
      (description "贴片排阻")
      (libsource (lib "RES") (part "0603*4  1KΩ (102) 5%"))
    )
    (comp (ref "RP4")
      (value "1KΩ")
      (footprint "0603_Rx4")
      (description "贴片排阻")
      (libsource (lib "RES") (part "0603*4  1KΩ (102) 5%"))
    )
    (comp (ref "RP5")
      (value "1KΩ")
      (footprint "0603_Rx4")
      (description "贴片排阻")
      (libsource (lib "RES") (part "0603*4  1KΩ (102) 5%"))
    )
    (comp (ref "RP6")
      (value "1KΩ")
      (footprint "0603_Rx4")
      (description "贴片排阻")
      (libsource (lib "RES") (part "0603*4  1KΩ (102) 5%"))
    )
    (comp (ref "RP7")
      (value "10KΩ")
      (footprint "0603_Rx4")
      (description "贴片排阻")
      (libsource (lib "RES") (part "0603*4  1KΩ (102) 5%"))
    )
    (comp (ref "RP8")
      (value "10KΩ")
      (footprint "0603_Rx4")
      (description "贴片排阻")
      (libsource (lib "RES") (part "0603*4  1KΩ (102) 5%"))
    )
    (comp (ref "RP9")
      (value "1KΩ")
      (footprint "0603_Rx4")
      (description "贴片排阻")
      (libsource (lib "RES") (part "0603*4  1KΩ (102) 5%"))
    )
    (comp (ref "S1")
      (value "SW DIP-4")
      (footprint "SO8_N")
      (description "DIP Switch, 4 Position, SPST")
      (fields (field (name "PUBLISHER") "Altium Limited"))
      (libsource (lib "Miscellaneous Devices") (part "SW DIP-4"))
    )
    (comp (ref "SW1")
      (value "3x6x5")
      (footprint "TSW SMD-3*6*2.5")
      (description "3x6轻触开关")
      (fields (field (name "版权归属") "源创客"))
      (libsource (lib "5.1   - 按键-开关") (part "TSW 3x6"))
    )
    (comp (ref "SW2")
      (value "3x6x5")
      (footprint "TSW SMD-3*6*2.5")
      (description "3x6轻触开关")
      (fields (field (name "版权归属") "源创客"))
      (libsource (lib "5.1   - 按键-开关") (part "TSW 3x6"))
    )
    (comp (ref "SW3")
      (value "3x6x5")
      (footprint "TSW SMD-3*6*2.5")
      (description "3x6轻触开关")
      (fields (field (name "版权归属") "源创客"))
      (libsource (lib "5.1   - 按键-开关") (part "TSW 3x6"))
    )
    (comp (ref "SW4")
      (value "3x6x5")
      (footprint "TSW SMD-3*6*2.5")
      (description "3x6轻触开关")
      (fields (field (name "版权归属") "源创客"))
      (libsource (lib "5.1   - 按键-开关") (part "TSW 3x6"))
    )
    (comp (ref "U1")
      (value "USR-GPRS232-7S3_Lib_V1.0")
      (footprint "USERGPRS")
      (libsource (lib "USR-GPRS232-7S3_Lib_V1.0") (part "USR-GPRS232-7S3_Lib_V1.0"))
    )
    (comp (ref "U2")
      (value "STM32F103RCT6")
      (footprint "LQFP-64_10x10x05P")
      (description "ARM")
      (libsource (lib "MCU") (part "STM32F103RCT6"))
    )
    (comp (ref "U3")
      (value "STC15W4K56S4 LQFP48")
      (footprint "LQFP48")
      (libsource (lib "WegeV1") (part "STC15W4K60S4 LQFP48"))
    )
    (comp (ref "U4") (value "USR-K3 V2") (footprint "USERKX") (libsource (lib "USR-Kx") (part "USR-K3 V2")))
    (comp (ref "U5") (value "ULN2803") (footprint "SOP18") (libsource (lib "WegeV1") (part "ULN2803")))
    (comp (ref "U6")
      (value "LM2576SX-5.0")
      (footprint "TO-263-5")
      (description "DC-DC芯片")
      (libsource (lib "Miscellaneous Devices LC") (part "LM2576SX-5.0_[C34465]"))
    )
    (comp (ref "U7") (value "78M05") (footprint "D-PAK") (libsource (lib "WegeV1") (part "78M05")))
    (comp (ref "U8")
      (value "EEPROM/AT24C256C-SSHL-T")
      (footprint "SOIC-8_150mil")
      (description "EEPROM")
      (libsource (lib "Miscellaneous Devices LC") (part "EEPROM/AT24C256C-SSHL-T_[C6482]"))
    )
    (comp (ref "VR1")
      (value "LM1117-3.3")
      (footprint "SOT-223")
      (description "低压差线性稳压(LDO)")
      (libsource (lib "LDO") (part "SOT-223 AMS1117-3.3"))
    )
    (comp (ref "Y1")
      (value "8MHz")
      (footprint "SMD-5032_2P")
      (description "贴片晶振")
      (libsource (lib "CrystalOscillator") (part "SMD-5032_2P 8MHz 20ppm 20pF"))
    )
    (comp (ref "Y2")
      (value "32.768KHz")
      (footprint "SMD-3215_2P FC - 135")
      (description "贴片晶振")
      (libsource (lib "CrystalOscillator") (part "SMD-3215_2P 32.768KHz 20ppm 12.5pF"))
    )
  )
  (nets
    (net (code "1") (name "/BCRX") (class "Default")
      (node (ref "P7") (pin "4") (pinfunction "4_4") (pintype "passive"))
      (node (ref "R33") (pin "1") (pinfunction "1_1") (pintype "passive"))
    )
    (net (code "2") (name "/BCTX") (class "Default")
      (node (ref "P7") (pin "5") (pinfunction "5_5") (pintype "passive"))
      (node (ref "R34") (pin "1") (pinfunction "1_1") (pintype "passive"))
    )
    (net (code "3") (name "/BOOT0") (class "Default")
      (node (ref "R25") (pin "2") (pinfunction "2_2") (pintype "passive"))
      (node (ref "U2") (pin "60") (pinfunction "BOOT0_60") (pintype "input"))
    )
    (net (code "4") (name "/BOOT1") (class "Default")
      (node (ref "R24") (pin "2") (pinfunction "2_2") (pintype "passive"))
      (node (ref "U2") (pin "28") (pinfunction "PB2_28") (pintype "bidirectional"))
    )
    (net (code "5") (name "/BUZZOUT") (class "Default")
      (node (ref "P7") (pin "9") (pinfunction "9_9") (pintype "passive"))
      (node (ref "R36") (pin "2") (pinfunction "2_2") (pintype "passive"))
    )
    (net (code "6") (name "/CODERXD3") (class "Default")
      (node (ref "R34") (pin "2") (pinfunction "2_2") (pintype "passive"))
      (node (ref "U2") (pin "30") (pinfunction "PB11_30") (pintype "bidirectional"))
    )
    (net (code "7") (name "/CODETXD3") (class "Default")
      (node (ref "R33") (pin "2") (pinfunction "2_2") (pintype "passive"))
      (node (ref "U2") (pin "29") (pinfunction "PB10_29") (pintype "bidirectional"))
    )
    (net (code "8") (name "/CUP1") (class "Default")
      (node (ref "R30") (pin "2") (pinfunction "2_2") (pintype "passive"))
      (node (ref "RP4") (pin "6") (pinfunction "6_6") (pintype "passive"))
      (node (ref "U3") (pin "5") (pinfunction "P1.0/ADC0/CCP1/RXD2_5") (pintype "passive"))
    )
    (net (code "9") (name "/CUP2") (class "Default")
      (node (ref "U3") (pin "14") (pinfunction "P5.4/RST/MCLKO/SS_3/CMP-_14") (pintype "passive"))
    )
    (net (code "10") (name "/CUP3") (class "Default")
      (node (ref "R31") (pin "2") (pinfunction "2_2") (pintype "passive"))
      (node (ref "RP5") (pin "6") (pinfunction "6_6") (pintype "passive"))
      (node (ref "U3") (pin "8") (pinfunction "P1.2/ADC2/SS/ECI/CMPO_8") (pintype "passive"))
    )
    (net (code "11") (name "/CUP4") (class "Default")
      (node (ref "U3") (pin "2") (pinfunction "P0.5/AD5/T4_2") (pintype "passive"))
    )
    (net (code "12") (name "/CUP5") (class "Default")
      (node (ref "R32") (pin "2") (pinfunction "2_2") (pintype "passive"))
      (node (ref "RP6") (pin "6") (pinfunction "6_6") (pintype "passive"))
      (node (ref "U3") (pin "11") (pinfunction "P1.5/ADC5/SCLK_11") (pintype "passive"))
    )
    (net (code "13") (name "/D+") (class "Default")
      (node (ref "P7") (pin "6") (pinfunction "6_6") (pintype "passive"))
    )
    (net (code "14") (name "/D-") (class "Default")
      (node (ref "P7") (pin "7") (pinfunction "7_7") (pintype "passive"))
    )
    (net (code "15") (name "/DIP_1") (class "Default")
      (node (ref "RP8") (pin "4") (pinfunction "4_4") (pintype "passive"))
      (node (ref "S1") (pin "8") (pinfunction "B1_8") (pintype "passive"))
      (node (ref "U2") (pin "20") (pinfunction "PA4_20") (pintype "bidirectional"))
    )
    (net (code "16") (name "/DIP_2") (class "Default")
      (node (ref "RP8") (pin "3") (pinfunction "3_3") (pintype "passive"))
      (node (ref "S1") (pin "7") (pinfunction "B2_7") (pintype "passive"))
      (node (ref "U2") (pin "21") (pinfunction "PA5_21") (pintype "bidirectional"))
    )
    (net (code "17") (name "/DIP_3") (class "Default")
      (node (ref "RP8") (pin "2") (pinfunction "2_2") (pintype "passive"))
      (node (ref "S1") (pin "6") (pinfunction "B3_6") (pintype "passive"))
      (node (ref "U2") (pin "22") (pinfunction "PA6_22") (pintype "bidirectional"))
    )
    (net (code "18") (name "/DIP_4") (class "Default")
      (node (ref "RP8") (pin "1") (pinfunction "1_1") (pintype "passive"))
      (node (ref "S1") (pin "5") (pinfunction "B4_5") (pintype "passive"))
      (node (ref "U2") (pin "23") (pinfunction "PA7_23") (pintype "bidirectional"))
    )
    (net (code "19") (name "/ETHNETRXD5 1") (class "Default")
      (node (ref "R17") (pin "1") (pinfunction "1_1") (pintype "passive"))
      (node (ref "U2") (pin "54") (pinfunction "PD2_54") (pintype "bidirectional"))
    )
    (net (code "20") (name "/ETHNETRXD5 2") (class "Default")
      (node (ref "R15") (pin "2") (pinfunction "2_2") (pintype "passive"))
      (node (ref "U4") (pin "8") (pinfunction "RXD_8") (pintype "passive"))
    )
    (net (code "21") (name "/ETHNETTXD5 1") (class "Default")
      (node (ref "R15") (pin "1") (pinfunction "1_1") (pintype "passive"))
      (node (ref "U2") (pin "53") (pinfunction "PC12_53") (pintype "bidirectional"))
    )
    (net (code "22") (name "/ETHNETTXD5 2") (class "Default")
      (node (ref "R17") (pin "2") (pinfunction "2_2") (pintype "passive"))
      (node (ref "U4") (pin "9") (pinfunction "TXD_9") (pintype "passive"))
    )
    (net (code "23") (name "/EXVALVE1") (class "Default")
      (node (ref "RP2") (pin "4") (pinfunction "4_4") (pintype "passive"))
      (node (ref "U3") (pin "44") (pinfunction "P0.1/AD1/TXD3_44") (pintype "passive"))
      (node (ref "U5") (pin "4") (pinfunction "4A_4") (pintype "passive"))
    )
    (net (code "24") (name "/EXVALVE2") (class "Default")
      (node (ref "RP1") (pin "1") (pinfunction "1_1") (pintype "passive"))
      (node (ref "U3") (pin "43") (pinfunction "P0.0/AD0/RXD3_43") (pintype "passive"))
      (node (ref "U5") (pin "5") (pinfunction "5A_5") (pintype "passive"))
    )
    (net (code "25") (name "/EXVALVE3") (class "Default")
      (node (ref "RP1") (pin "2") (pinfunction "2_2") (pintype "passive"))
      (node (ref "U3") (pin "42") (pinfunction "P4.6/RXD2_2_42") (pintype "passive"))
      (node (ref "U5") (pin "6") (pinfunction "6A_6") (pintype "passive"))
    )
    (net (code "26") (name "/GLED1") (class "Default")
      (node (ref "RP4") (pin "7") (pinfunction "7_7") (pintype "passive"))
      (node (ref "U3") (pin "4") (pinfunction "P0.7/AD7/T3_4") (pintype "passive"))
    )
    (net (code "27") (name "/GLED2") (class "Default")
      (node (ref "U3") (pin "13") (pinfunction "P1.7/ADC7/TXD_3/XTAL1_13") (pintype "passive"))
    )
    (net (code "28") (name "/GLED3") (class "Default")
      (node (ref "RP5") (pin "7") (pinfunction "7_7") (pintype "passive"))
      (node (ref "U3") (pin "7") (pinfunction "P4.7/TXD2_2_7") (pintype "passive"))
    )
    (net (code "29") (name "/GLED4") (class "Default")
      (node (ref "U3") (pin "1") (pinfunction "P5.3/TXT4_2_1") (pintype "passive"))
    )
    (net (code "30") (name "/GLED5") (class "Default")
      (node (ref "RP6") (pin "7") (pinfunction "7_7") (pintype "passive"))
      (node (ref "U3") (pin "10") (pinfunction "P1.4/ADC4/MISO_10") (pintype "passive"))
    )
    (net (code "31") (name "/GPRSRXD1 1") (class "Default")
      (node (ref "R8") (pin "1") (pinfunction "1_1") (pintype "passive"))
      (node (ref "U2") (pin "43") (pinfunction "PA10_43") (pintype "bidirectional"))
    )
    (net (code "32") (name "/GPRSRXD1 2") (class "Default")
      (node (ref "R9") (pin "2") (pinfunction "2_2") (pintype "passive"))
      (node (ref "U1") (pin "7") (pinfunction "URXD1_7") (pintype "passive"))
    )
    (net (code "33") (name "/GPRSTXD1 1") (class "Default")
      (node (ref "R9") (pin "1") (pinfunction "1_1") (pintype "passive"))
      (node (ref "U2") (pin "42") (pinfunction "PA9_42") (pintype "bidirectional"))
    )
    (net (code "34") (name "/GPRSTXD1 2") (class "Default")
      (node (ref "R8") (pin "2") (pinfunction "2_2") (pintype "passive"))
      (node (ref "U1") (pin "6") (pinfunction "UTXD1_6") (pintype "passive"))
    )
    (net (code "35") (name "/I2C1_SCL") (class "Default")
      (node (ref "R49") (pin "1") (pinfunction "1_1") (pintype "passive"))
      (node (ref "U2") (pin "58") (pinfunction "PB6_58") (pintype "bidirectional"))
      (node (ref "U8") (pin "6") (pinfunction "SCL_6") (pintype "passive"))
    )
    (net (code "36") (name "/I2C1_SDA") (class "Default")
      (node (ref "R48") (pin "1") (pinfunction "1_1") (pintype "passive"))
      (node (ref "U2") (pin "59") (pinfunction "PB7_59") (pintype "bidirectional"))
      (node (ref "U8") (pin "5") (pinfunction "SDA_5") (pintype "passive"))
    )
    (net (code "37") (name "/INT0") (class "Default")
      (node (ref "U3") (pin "21") (pinfunction "P3.2/INT0_21") (pintype "passive"))
    )
    (net (code "38") (name "/ISPRXD") (class "Default")
      (node (ref "JP2") (pin "3") (pinfunction "3_3") (pintype "passive"))
      (node (ref "U3") (pin "19") (pinfunction "P3.0/RXD/~{INT4}/T2CLKO_19") (pintype "passive"))
    )
    (net (code "39") (name "/ISPTXD") (class "Default")
      (node (ref "JP2") (pin "2") (pinfunction "2_2") (pintype "passive"))
      (node (ref "U3") (pin "20") (pinfunction "P3.1/TXD/T2_20") (pintype "passive"))
    )
    (net (code "40") (name "/KB CLK") (class "Default")
      (node (ref "P7") (pin "11") (pinfunction "11_11") (pintype "passive"))
    )
    (net (code "41") (name "/KB DATA") (class "Default")
      (node (ref "P7") (pin "8") (pinfunction "8_8") (pintype "passive"))
    )
    (net (code "42") (name "/KEY IN") (class "Default")
      (node (ref "R37") (pin "2") (pinfunction "2_2") (pintype "passive"))
      (node (ref "U2") (pin "24") (pinfunction "PC4_24") (pintype "bidirectional"))
    )
    (net (code "43") (name "/KEY_0") (class "Default")
      (node (ref "RP7") (pin "1") (pinfunction "1_1") (pintype "passive"))
      (node (ref "SW4") (pin "2") (pinfunction "2_2") (pintype "passive"))
      (node (ref "U2") (pin "34") (pinfunction "PB13_34") (pintype "bidirectional"))
    )
    (net (code "44") (name "/KEY_1") (class "Default")
      (node (ref "RP7") (pin "2") (pinfunction "2_2") (pintype "passive"))
      (node (ref "SW2") (pin "2") (pinfunction "2_2") (pintype "passive"))
      (node (ref "U2") (pin "35") (pinfunction "PB14_35") (pintype "bidirectional"))
    )
    (net (code "45") (name "/KEY_2") (class "Default")
      (node (ref "RP7") (pin "3") (pinfunction "3_3") (pintype "passive"))
      (node (ref "SW3") (pin "2") (pinfunction "2_2") (pintype "passive"))
      (node (ref "U2") (pin "36") (pinfunction "PB15_36") (pintype "bidirectional"))
    )
    (net (code "46") (name "/LED") (class "Default")
      (node (ref "D21") (pin "K") (pinfunction "K_K") (pintype "passive"))
      (node (ref "U3") (pin "29") (pinfunction "P4.1/MISO_3_29") (pintype "passive"))
    )
    (net (code "47") (name "/LEDOUT") (class "Default")
      (node (ref "P7") (pin "10") (pinfunction "10_10") (pintype "passive"))
    )
    (net (code "48") (name "/LED_0") (class "Default")
      (node (ref "D14") (pin "K") (pinfunction "K_K") (pintype "passive"))
      (node (ref "U2") (pin "8") (pinfunction "PC0_8") (pintype "bidirectional"))
    )
    (net (code "49") (name "/LED_1") (class "Default")
      (node (ref "D16") (pin "K") (pinfunction "K_K") (pintype "passive"))
      (node (ref "U2") (pin "9") (pinfunction "PC1_9") (pintype "bidirectional"))
    )
    (net (code "50") (name "/LED_2") (class "Default")
      (node (ref "D23") (pin "K") (pinfunction "K_K") (pintype "passive"))
      (node (ref "U2") (pin "10") (pinfunction "PC2_10") (pintype "bidirectional"))
    )
    (net (code "51") (name "/LED_3") (class "Default")
      (node (ref "D22") (pin "K") (pinfunction "K_K") (pintype "passive"))
      (node (ref "U2") (pin "11") (pinfunction "PC3_11") (pintype "bidirectional"))
    )
    (net (code "52") (name "/NC") (class "Default")
      (node (ref "P7") (pin "1") (pinfunction "1_1") (pintype "passive"))
    )
    (net (code "53") (name "/OSC32_IN1") (class "Default")
      (node (ref "C5") (pin "2") (pinfunction "2_2") (pintype "passive"))
      (node (ref "U2") (pin "3") (pinfunction "PC14-OSC32_IN_3") (pintype "bidirectional"))
      (node (ref "Y2") (pin "1") (pinfunction "OSC1_1") (pintype "passive"))
    )
    (net (code "54") (name "/OSC32_OUT1") (class "Default")
      (node (ref "C6") (pin "2") (pinfunction "2_2") (pintype "passive"))
      (node (ref "U2") (pin "4") (pinfunction "PC15-OSC32_OUT_4") (pintype "bidirectional"))
      (node (ref "Y2") (pin "2") (pinfunction "OSC2_2") (pintype "passive"))
    )
    (net (code "55") (name "/OSC_IN2") (class "Default")
      (node (ref "C2") (pin "2") (pinfunction "2_2") (pintype "passive"))
      (node (ref "R26") (pin "2") (pinfunction "2_2") (pintype "passive"))
      (node (ref "U2") (pin "5") (pinfunction "PD0-OSC_IN_5") (pintype "bidirectional"))
      (node (ref "Y1") (pin "1") (pinfunction "OSC1_1") (pintype "passive"))
    )
    (net (code "56") (name "/OSC_OUT2") (class "Default")
      (node (ref "C3") (pin "2") (pinfunction "2_2") (pintype "passive"))
      (node (ref "R26") (pin "1") (pinfunction "1_1") (pintype "passive"))
      (node (ref "U2") (pin "6") (pinfunction "PD1_6") (pintype "bidirectional"))
      (node (ref "Y1") (pin "2") (pinfunction "OSC2_2") (pintype "passive"))
    )
    (net (code "57") (name "/OUT5V") (class "Default")
      (node (ref "RP1") (pin "4") (pinfunction "4_4") (pintype "passive"))
      (node (ref "U3") (pin "40") (pinfunction "P2.7/A15/CCP2_3_40") (pintype "passive"))
      (node (ref "U5") (pin "8") (pinfunction "8A_8") (pintype "passive"))
    )
    (net (code "58") (name "/PRESSADC1") (class "Default")
      (node (ref "C34") (pin "2") (pinfunction "2_2") (pintype "passive"))
      (node (ref "R45") (pin "1") (pinfunction "1_1") (pintype "passive"))
      (node (ref "R46") (pin "2") (pinfunction "2_2") (pintype "passive"))
      (node (ref "U2") (pin "25") (pinfunction "PC5_25") (pintype "bidirectional"))
    )
    (net (code "59") (name "/PRESSADC2") (class "Default")
      (node (ref "C33") (pin "2") (pinfunction "2_2") (pintype "passive"))
      (node (ref "R47") (pin "1") (pinfunction "1_1") (pintype "passive"))
      (node (ref "R50") (pin "2") (pinfunction "2_2") (pintype "passive"))
      (node (ref "U2") (pin "26") (pinfunction "PB0_26") (pintype "bidirectional"))
    )
    (net (code "60") (name "/PRESSADC3") (class "Default")
      (node (ref "C48") (pin "2") (pinfunction "2_2") (pintype "passive"))
      (node (ref "R51") (pin "1") (pinfunction "1_1") (pintype "passive"))
      (node (ref "R52") (pin "2") (pinfunction "2_2") (pintype "passive"))
      (node (ref "U2") (pin "27") (pinfunction "PB1_27") (pintype "bidirectional"))
    )
    (net (code "61") (name "/PUMP1") (class "Default")
      (node (ref "RP2") (pin "1") (pinfunction "1_1") (pintype "passive"))
      (node (ref "U3") (pin "47") (pinfunction "P0.4/AD4/T4CLKO_47") (pintype "passive"))
      (node (ref "U5") (pin "1") (pinfunction "1A_1") (pintype "passive"))
    )
    (net (code "62") (name "/PUMP2") (class "Default")
      (node (ref "RP2") (pin "2") (pinfunction "2_2") (pintype "passive"))
      (node (ref "U3") (pin "46") (pinfunction "P0.3/AD3/TXD4_46") (pintype "passive"))
      (node (ref "U5") (pin "2") (pinfunction "2A_2") (pintype "passive"))
    )
    (net (code "63") (name "/PUMP3") (class "Default")
      (node (ref "RP2") (pin "3") (pinfunction "3_3") (pintype "passive"))
      (node (ref "U3") (pin "45") (pinfunction "P0.2/AD2/RXD4_45") (pintype "passive"))
      (node (ref "U5") (pin "3") (pinfunction "3A_3") (pintype "passive"))
    )
    (net (code "64") (name "/RESET") (class "Default")
      (node (ref "C12") (pin "2") (pinfunction "2_2") (pintype "passive"))
      (node (ref "R35") (pin "1") (pinfunction "1_1") (pintype "passive"))
      (node (ref "SW1") (pin "2") (pinfunction "2_2") (pintype "passive"))
      (node (ref "U2") (pin "7") (pinfunction "NRST_7") (pintype "bidirectional"))
    )
    (net (code "65") (name "/RLED1") (class "Default")
      (node (ref "RP4") (pin "8") (pinfunction "8_8") (pintype "passive"))
      (node (ref "U3") (pin "3") (pinfunction "P0.6/AD6/T3CLKO_3") (pintype "passive"))
    )
    (net (code "66") (name "/RLED2") (class "Default")
      (node (ref "U3") (pin "12") (pinfunction "P1.6/ADC6/RXD_3/XTAL2/MCLKO_2_12") (pintype "passive"))
    )
    (net (code "67") (name "/RLED3") (class "Default")
      (node (ref "RP5") (pin "8") (pinfunction "8_8") (pintype "passive"))
      (node (ref "U3") (pin "6") (pinfunction "P1.1/ADC1/CCP0/TXD2_6") (pintype "passive"))
    )
    (net (code "68") (name "/RLED4") (class "Default")
      (node (ref "U3") (pin "48") (pinfunction "P5.2/RXD4_2_48") (pintype "passive"))
    )
    (net (code "69") (name "/RLED5") (class "Default")
      (node (ref "RP6") (pin "8") (pinfunction "8_8") (pintype "passive"))
      (node (ref "U3") (pin "9") (pinfunction "P1.3/ADC3/MOSI_9") (pintype "passive"))
    )
    (net (code "70") (name "/SCREENRX2 1") (class "Default")
      (node (ref "R39") (pin "2") (pinfunction "2_2") (pintype "passive"))
      (node (ref "U2") (pin "17") (pinfunction "PA3_17") (pintype "bidirectional"))
    )
    (net (code "71") (name "/SCREENRX2 2") (class "Default")
      (node (ref "P9") (pin "3") (pinfunction "3_3") (pintype "passive"))
      (node (ref "R38") (pin "1") (pinfunction "1_1") (pintype "passive"))
    )
    (net (code "72") (name "/SCREENTX2 1") (class "Default")
      (node (ref "R38") (pin "2") (pinfunction "2_2") (pintype "passive"))
      (node (ref "U2") (pin "16") (pinfunction "PA2_16") (pintype "bidirectional"))
    )
    (net (code "73") (name "/SCREENTX2 2") (class "Default")
      (node (ref "P9") (pin "4") (pinfunction "4_4") (pintype "passive"))
      (node (ref "R39") (pin "1") (pinfunction "1_1") (pintype "passive"))
    )
    (net (code "74") (name "/SLAVERXD4 1") (class "Default")
      (node (ref "R18") (pin "2") (pinfunction "2_2") (pintype "passive"))
      (node (ref "R19") (pin "2") (pinfunction "2_2") (pintype "passive"))
      (node (ref "U2") (pin "52") (pinfunction "PC11_52") (pintype "bidirectional"))
    )
    (net (code "75") (name "/SLAVETXD4 1") (class "Default")
      (node (ref "R20") (pin "2") (pinfunction "2_2") (pintype "passive"))
      (node (ref "R23") (pin "2") (pinfunction "2_2") (pintype "passive"))
      (node (ref "U2") (pin "51") (pinfunction "PC10_51") (pintype "bidirectional"))
    )
    (net (code "76") (name "/SP36RXD1 2") (class "Default")
      (node (ref "R23") (pin "1") (pinfunction "1_1") (pintype "passive"))
      (node (ref "U3") (pin "27") (pinfunction "P3.6/~{INT2}/RXD_2/CCP1_2_27") (pintype "passive"))
    )
    (net (code "77") (name "/SP37TXD1 2") (class "Default")
      (node (ref "R18") (pin "1") (pinfunction "1_1") (pintype "passive"))
      (node (ref "U3") (pin "28") (pinfunction "P3.7/~{INT3}/TXD_2/CCP2/CCP2_2_28") (pintype "passive"))
    )
    (net (code "78") (name "/SP50RXD32") (class "Default")
      (node (ref "R20") (pin "1") (pinfunction "1_1") (pintype "passive"))
      (node (ref "U3") (pin "24") (pinfunction "P5.0/RXD3_2_24") (pintype "passive"))
    )
    (net (code "79") (name "/SP51TXD32") (class "Default")
      (node (ref "R19") (pin "1") (pinfunction "1_1") (pintype "passive"))
      (node (ref "U3") (pin "25") (pinfunction "P5.1/TXD3_2_25") (pintype "passive"))
    )
    (net (code "80") (name "/SPARE") (class "Default")
      (node (ref "U3") (pin "41") (pinfunction "P4.5/ALE/CCP5_41") (pintype "passive"))
    )
    (net (code "81") (name "/SWCLK") (class "Default")
      (node (ref "JP1") (pin "3") (pinfunction "3_3") (pintype "passive"))
      (node (ref "U2") (pin "49") (pinfunction "PA14_49") (pintype "bidirectional"))
    )
    (net (code "82") (name "/SWDIO") (class "Default")
      (node (ref "JP1") (pin "2") (pinfunction "2_2") (pintype "passive"))
      (node (ref "U2") (pin "46") (pinfunction "PA13_46") (pintype "bidirectional"))
    )
    (net (code "83") (name "/ULN1_OUT1") (class "Default")
      (node (ref "D5") (pin "K") (pinfunction "K_K") (pintype "passive"))
      (node (ref "REL1") (pin "1") (pintype "passive"))
      (node (ref "U5") (pin "18") (pinfunction "1B_18") (pintype "passive"))
    )
    (net (code "84") (name "/ULN1_OUT2") (class "Default")
      (node (ref "D6") (pin "K") (pinfunction "K_K") (pintype "passive"))
      (node (ref "REL2") (pin "1") (pintype "passive"))
      (node (ref "U5") (pin "17") (pinfunction "2B_17") (pintype "passive"))
    )
    (net (code "85") (name "/ULN1_OUT3") (class "Default")
      (node (ref "D7") (pin "K") (pinfunction "K_K") (pintype "passive"))
      (node (ref "REL3") (pin "1") (pintype "passive"))
      (node (ref "U5") (pin "16") (pinfunction "3B_16") (pintype "passive"))
    )
    (net (code "86") (name "/ULN1_OUT4") (class "Default")
      (node (ref "D8") (pin "K") (pinfunction "K_K") (pintype "passive"))
      (node (ref "REL4") (pin "1") (pintype "passive"))
      (node (ref "U5") (pin "15") (pinfunction "4B_15") (pintype "passive"))
    )
    (net (code "87") (name "/ULN1_OUT5") (class "Default")
      (node (ref "D9") (pin "K") (pinfunction "K_K") (pintype "passive"))
      (node (ref "REL5") (pin "1") (pintype "passive"))
      (node (ref "U5") (pin "14") (pinfunction "5B_14") (pintype "passive"))
    )
    (net (code "88") (name "/ULN1_OUT6") (class "Default")
      (node (ref "D10") (pin "K") (pinfunction "K_K") (pintype "passive"))
      (node (ref "REL6") (pin "1") (pintype "passive"))
      (node (ref "U5") (pin "13") (pinfunction "6B_13") (pintype "passive"))
    )
    (net (code "89") (name "/ULN1_OUT7") (class "Default")
      (node (ref "D11") (pin "K") (pinfunction "K_K") (pintype "passive"))
      (node (ref "REL7") (pin "1") (pintype "passive"))
      (node (ref "U5") (pin "12") (pinfunction "7B_12") (pintype "passive"))
    )
    (net (code "90") (name "/ULN1_OUT8") (class "Default")
      (node (ref "D12") (pin "K") (pinfunction "K_K") (pintype "passive"))
      (node (ref "REL8") (pin "1") (pintype "passive"))
      (node (ref "U5") (pin "11") (pinfunction "8B_11") (pintype "passive"))
    )
    (net (code "91") (name "/UNLOCK") (class "Default")
      (node (ref "R16") (pin "1") (pinfunction "1_1") (pintype "passive"))
      (node (ref "RP1") (pin "3") (pinfunction "3_3") (pintype "passive"))
      (node (ref "U5") (pin "7") (pinfunction "7A_7") (pintype "passive"))
    )
    (net (code "92") (name "/VBAT") (class "Default")
      (node (ref "C49") (pin "2") (pinfunction "2_2") (pintype "passive"))
      (node (ref "D27") (pin "2") (pinfunction "K_2") (pintype "passive"))
      (node (ref "D28") (pin "2") (pinfunction "K_2") (pintype "passive"))
      (node (ref "U2") (pin "1") (pinfunction "VBAT_1") (pintype "power_in"))
    )
    (net (code "93") (name "/WATERVCC") (class "Default")
      (node (ref "J8") (pin "2") (pinfunction "2_2") (pintype "passive"))
      (node (ref "R21") (pin "1") (pinfunction "1_1") (pintype "passive"))
      (node (ref "REL8") (pin "3") (pintype "passive"))
    )
    (net (code "94") (name "/WATSTATUS1") (class "Default")
      (node (ref "RP3") (pin "5") (pinfunction "5_5") (pintype "passive"))
      (node (ref "U3") (pin "34") (pinfunction "P2.1/A9/SCLK_2_34") (pintype "passive"))
    )
    (net (code "95") (name "/WATSTATUS2") (class "Default")
      (node (ref "U3") (pin "33") (pinfunction "P2.0/A8/RSTOUT_LOW_33") (pintype "passive"))
    )
    (net (code "96") (name "/WATSTATUS3") (class "Default")
      (node (ref "RP3") (pin "6") (pinfunction "6_6") (pintype "passive"))
      (node (ref "U3") (pin "32") (pinfunction "P4.4/~{RD}/CCP4_32") (pintype "passive"))
    )
    (net (code "97") (name "/WATSTATUS4") (class "Default")
      (node (ref "RP3") (pin "7") (pinfunction "7_7") (pintype "passive"))
      (node (ref "U3") (pin "31") (pinfunction "P4.3/SCLK_3_31") (pintype "passive"))
    )
    (net (code "98") (name "/WATSTATUS5") (class "Default")
      (node (ref "RP3") (pin "8") (pinfunction "8_8") (pintype "passive"))
      (node (ref "U3") (pin "30") (pinfunction "P4.2/~{WR}/CCP3_30") (pintype "passive"))
    )
    (net (code "99") (name "GND") (class "Default")
      (node (ref "C1") (pin "2") (pinfunction "2_2") (pintype "passive"))
      (node (ref "C10") (pin "2") (pinfunction "2_2") (pintype "passive"))
      (node (ref "C11") (pin "2") (pinfunction "2_2") (pintype "passive"))
      (node (ref "C12") (pin "1") (pinfunction "1_1") (pintype "passive"))
      (node (ref "C16") (pin "2") (pinfunction "2_2") (pintype "passive"))
      (node (ref "C17") (pin "2") (pinfunction "2_2") (pintype "passive"))
      (node (ref "C18") (pin "2") (pinfunction "2_2") (pintype "passive"))
      (node (ref "C19") (pin "2") (pinfunction "2_2") (pintype "passive"))
      (node (ref "C2") (pin "1") (pinfunction "1_1") (pintype "passive"))
      (node (ref "C20") (pin "1") (pinfunction "1_1") (pintype "passive"))
      (node (ref "C21") (pin "2") (pinfunction "2_2") (pintype "passive"))
      (node (ref "C22") (pin "2") (pinfunction "2_2") (pintype "passive"))
      (node (ref "C23") (pin "2") (pinfunction "2_2") (pintype "passive"))
      (node (ref "C24") (pin "1") (pinfunction "1_1") (pintype "passive"))
      (node (ref "C25") (pin "1") (pinfunction "1_1") (pintype "passive"))
      (node (ref "C26") (pin "1") (pinfunction "1_1") (pintype "passive"))
      (node (ref "C27") (pin "1") (pinfunction "1_1") (pintype "passive"))
      (node (ref "C28") (pin "1") (pinfunction "1_1") (pintype "passive"))
      (node (ref "C29") (pin "1") (pinfunction "1_1") (pintype "passive"))
      (node (ref "C3") (pin "1") (pinfunction "1_1") (pintype "passive"))
      (node (ref "C30") (pin "1") (pinfunction "1_1") (pintype "passive"))
      (node (ref "C31") (pin "1") (pinfunction "1_1") (pintype "passive"))
      (node (ref "C32") (pin "1") (pinfunction "1_1") (pintype "passive"))
      (node (ref "C33") (pin "1") (pinfunction "1_1") (pintype "passive"))
      (node (ref "C34") (pin "1") (pinfunction "1_1") (pintype "passive"))
      (node (ref "C35") (pin "1") (pinfunction "1_1") (pintype "passive"))
      (node (ref "C36") (pin "2") (pinfunction "2_2") (pintype "passive"))
      (node (ref "C37") (pin "2") (pinfunction "2_2") (pintype "passive"))
      (node (ref "C38") (pin "2") (pinfunction "2_2") (pintype "passive"))
      (node (ref "C39") (pin "2") (pinfunction "2_2") (pintype "passive"))
      (node (ref "C4") (pin "2") (pinfunction "2_2") (pintype "passive"))
      (node (ref "C40") (pin "2") (pinfunction "2_2") (pintype "passive"))
      (node (ref "C41") (pin "2") (pinfunction "2_2") (pintype "passive"))
      (node (ref "C42") (pin "2") (pinfunction "2_2") (pintype "passive"))
      (node (ref "C43") (pin "1") (pinfunction "1_1") (pintype "passive"))
      (node (ref "C44") (pin "2") (pinfunction "2_2") (pintype "passive"))
      (node (ref "C45") (pin "2") (pinfunction "2_2") (pintype "passive"))
      (node (ref "C46") (pin "1") (pinfunction "1_1") (pintype "passive"))
      (node (ref "C47") (pin "1") (pinfunction "1_1") (pintype "passive"))
      (node (ref "C48") (pin "1") (pinfunction "1_1") (pintype "passive"))
      (node (ref "C49") (pin "1") (pinfunction "1_1") (pintype "passive"))
      (node (ref "C5") (pin "1") (pinfunction "1_1") (pintype "passive"))
      (node (ref "C50") (pin "2") (pinfunction "2_2") (pintype "passive"))
      (node (ref "C6") (pin "1") (pinfunction "1_1") (pintype "passive"))
      (node (ref "C7") (pin "2") (pinfunction "2_2") (pintype "passive"))
      (node (ref "C8") (pin "2") (pinfunction "2_2") (pintype "passive"))
      (node (ref "C9") (pin "2") (pinfunction "2_2") (pintype "passive"))
      (node (ref "CR1") (pin "2") (pinfunction "DC-_2") (pintype "passive"))
      (node (ref "D25") (pin "1") (pinfunction "A_1") (pintype "passive"))
      (node (ref "J8") (pin "1") (pinfunction "1_1") (pintype "passive"))
      (node (ref "JP1") (pin "1") (pinfunction "1_1") (pintype "passive"))
      (node (ref "JP2") (pin "1") (pinfunction "1_1") (pintype "passive"))
      (node (ref "L1") (pin "3") (pinfunction "B_3") (pintype "passive"))
      (node (ref "NTC1") (pin "1") (pinfunction "1_1") (pintype "passive"))
      (node (ref "P1") (pin "1") (pinfunction "1_1") (pintype "passive"))
      (node (ref "P10") (pin "3") (pinfunction "3_3") (pintype "passive"))
      (node (ref "P10") (pin "6") (pinfunction "6_6") (pintype "passive"))
      (node (ref "P11") (pin "3") (pinfunction "3_3") (pintype "passive"))
      (node (ref "P11") (pin "6") (pinfunction "6_6") (pintype "passive"))
      (node (ref "P12") (pin "3") (pinfunction "3_3") (pintype "passive"))
      (node (ref "P12") (pin "6") (pinfunction "6_6") (pintype "passive"))
      (node (ref "P2") (pin "1") (pinfunction "1_1") (pintype "passive"))
      (node (ref "P3") (pin "1") (pinfunction "1_1") (pintype "passive"))
      (node (ref "P4") (pin "1") (pinfunction "1_1") (pintype "passive"))
      (node (ref "P5") (pin "1") (pinfunction "1_1") (pintype "passive"))
      (node (ref "P6") (pin "1") (pinfunction "1_1") (pintype "passive"))
      (node (ref "P7") (pin "3") (pinfunction "3_3") (pintype "passive"))
      (node (ref "P8") (pin "2") (pinfunction "2_2") (pintype "passive"))
      (node (ref "P8") (pin "5") (pinfunction "5_5") (pintype "passive"))
      (node (ref "P9") (pin "2") (pinfunction "2_2") (pintype "passive"))
      (node (ref "Q1") (pin "2") (pinfunction "E_2") (pintype "passive"))
      (node (ref "Q2") (pin "2") (pinfunction "E_2") (pintype "passive"))
      (node (ref "Q3") (pin "2") (pinfunction "E_2") (pintype "passive"))
      (node (ref "Q4") (pin "2") (pinfunction "E_2") (pintype "passive"))
      (node (ref "Q5") (pin "2") (pinfunction "E_2") (pintype "passive"))
      (node (ref "R24") (pin "1") (pinfunction "1_1") (pintype "passive"))
      (node (ref "R25") (pin "1") (pinfunction "1_1") (pintype "passive"))
      (node (ref "R40") (pin "1") (pinfunction "1_1") (pintype "passive"))
      (node (ref "R41") (pin "2") (pinfunction "2_2") (pintype "passive"))
      (node (ref "R42") (pin "2") (pinfunction "2_2") (pintype "passive"))
      (node (ref "R43") (pin "2") (pinfunction "2_2") (pintype "passive"))
      (node (ref "R46") (pin "1") (pinfunction "1_1") (pintype "passive"))
      (node (ref "R50") (pin "1") (pinfunction "1_1") (pintype "passive"))
      (node (ref "R52") (pin "1") (pinfunction "1_1") (pintype "passive"))
      (node (ref "R53") (pin "1") (pinfunction "1_1") (pintype "passive"))
      (node (ref "RP1") (pin "5") (pinfunction "5_5") (pintype "passive"))
      (node (ref "RP1") (pin "6") (pinfunction "6_6") (pintype "passive"))
      (node (ref "RP1") (pin "7") (pinfunction "7_7") (pintype "passive"))
      (node (ref "RP1") (pin "8") (pinfunction "8_8") (pintype "passive"))
      (node (ref "RP2") (pin "5") (pinfunction "5_5") (pintype "passive"))
      (node (ref "RP2") (pin "6") (pinfunction "6_6") (pintype "passive"))
      (node (ref "RP2") (pin "7") (pinfunction "7_7") (pintype "passive"))
      (node (ref "RP2") (pin "8") (pinfunction "8_8") (pintype "passive"))
      (node (ref "S1") (pin "1") (pinfunction "A1_1") (pintype "passive"))
      (node (ref "S1") (pin "2") (pinfunction "A2_2") (pintype "passive"))
      (node (ref "S1") (pin "3") (pinfunction "A3_3") (pintype "passive"))
      (node (ref "S1") (pin "4") (pinfunction "A4_4") (pintype "passive"))
      (node (ref "SW1") (pin "1") (pinfunction "1_1") (pintype "passive"))
      (node (ref "SW2") (pin "1") (pinfunction "1_1") (pintype "passive"))
      (node (ref "SW3") (pin "1") (pinfunction "1_1") (pintype "passive"))
      (node (ref "SW4") (pin "1") (pinfunction "1_1") (pintype "passive"))
      (node (ref "U1") (pin "11") (pinfunction "GND_11") (pintype "passive"))
      (node (ref "U1") (pin "12") (pinfunction "GND_12") (pintype "passive"))
      (node (ref "U2") (pin "12") (pinfunction "VSSA_12") (pintype "power_in"))
      (node (ref "U2") (pin "18") (pinfunction "VSS_4_18") (pintype "power_in"))
      (node (ref "U2") (pin "31") (pinfunction "VSS_1_31") (pintype "power_in"))
      (node (ref "U2") (pin "47") (pinfunction "VSS_2_47") (pintype "power_in"))
      (node (ref "U2") (pin "63") (pinfunction "VSS_3_63") (pintype "power_in"))
      (node (ref "U3") (pin "17") (pinfunction "GND_17") (pintype "passive"))
      (node (ref "U4") (pin "10") (pinfunction "GND_10") (pintype "passive"))
      (node (ref "U5") (pin "9") (pinfunction "GND_9") (pintype "passive"))
      (node (ref "U6") (pin "3") (pinfunction "GND_3") (pintype "power_in"))
      (node (ref "U6") (pin "5") (pinfunction "~{ON}/OFF_5") (pintype "input"))
      (node (ref "U7") (pin "2") (pinfunction "VSS_2") (pintype "passive"))
      (node (ref "U8") (pin "1") (pinfunction "A0_1") (pintype "passive"))
      (node (ref "U8") (pin "2") (pinfunction "A1_2") (pintype "passive"))
      (node (ref "U8") (pin "3") (pinfunction "A3_3") (pintype "passive"))
      (node (ref "U8") (pin "4") (pinfunction "GND_4") (pintype "passive"))
      (node (ref "U8") (pin "7") (pinfunction "WP_7") (pintype "passive"))
      (node (ref "VR1") (pin "1") (pinfunction "GND_1") (pintype "passive"))
    )
    (net (code "100") (name "GNDPUM") (class "Default")
      (node (ref "C13") (pin "2") (pinfunction "2_2") (pintype "passive"))
      (node (ref "C14") (pin "2") (pinfunction "2_2") (pintype "passive"))
      (node (ref "C15") (pin "2") (pinfunction "2_2") (pintype "passive"))
      (node (ref "J1") (pin "1") (pinfunction "1_1") (pintype "passive"))
      (node (ref "J2") (pin "1") (pinfunction "1_1") (pintype "passive"))
      (node (ref "J3") (pin "1") (pinfunction "1_1") (pintype "passive"))
      (node (ref "J4") (pin "1") (pinfunction "1_1") (pintype "passive"))
      (node (ref "J5") (pin "1") (pinfunction "1_1") (pintype "passive"))
      (node (ref "J6") (pin "1") (pinfunction "1_1") (pintype "passive"))
      (node (ref "J7") (pin "1") (pinfunction "1_1") (pintype "passive"))
      (node (ref "L1") (pin "4") (pinfunction "B_4") (pintype "passive"))
    )
    (net (code "101") (name "Net-(C36-Pad1)") (class "Default")
      (node (ref "C36") (pin "1") (pinfunction "1_1") (pintype "passive"))
      (node (ref "P4") (pin "5") (pinfunction "5_5") (pintype "passive"))
      (node (ref "R27") (pin "2") (pinfunction "2_2") (pintype "passive"))
    )
    (net (code "102") (name "Net-(C37-Pad1)") (class "Default")
      (node (ref "C37") (pin "1") (pinfunction "1_1") (pintype "passive"))
      (node (ref "P5") (pin "5") (pinfunction "5_5") (pintype "passive"))
      (node (ref "R28") (pin "2") (pinfunction "2_2") (pintype "passive"))
    )
    (net (code "103") (name "Net-(C38-Pad1)") (class "Default")
      (node (ref "C38") (pin "1") (pinfunction "1_1") (pintype "passive"))
      (node (ref "P6") (pin "5") (pinfunction "5_5") (pintype "passive"))
      (node (ref "R29") (pin "2") (pinfunction "2_2") (pintype "passive"))
    )
    (net (code "104") (name "Net-(CR1-DC+)") (class "Default")
      (node (ref "CR1") (pin "1") (pinfunction "DC+_1") (pintype "passive"))
      (node (ref "D28") (pin "1") (pinfunction "A_1") (pintype "passive"))
    )
    (net (code "105") (name "Net-(D5-PadA)") (class "Default")
      (node (ref "D5") (pin "A") (pinfunction "A_A") (pintype "passive"))
      (node (ref "R5") (pin "1") (pinfunction "1_1") (pintype "passive"))
    )
    (net (code "106") (name "Net-(D6-PadA)") (class "Default")
      (node (ref "D6") (pin "A") (pinfunction "A_A") (pintype "passive"))
      (node (ref "R6") (pin "1") (pinfunction "1_1") (pintype "passive"))
    )
    (net (code "107") (name "Net-(D7-PadA)") (class "Default")
      (node (ref "D7") (pin "A") (pinfunction "A_A") (pintype "passive"))
      (node (ref "R7") (pin "1") (pinfunction "1_1") (pintype "passive"))
    )
    (net (code "108") (name "Net-(D8-PadA)") (class "Default")
      (node (ref "D8") (pin "A") (pinfunction "A_A") (pintype "passive"))
      (node (ref "R10") (pin "1") (pinfunction "1_1") (pintype "passive"))
    )
    (net (code "109") (name "Net-(D9-PadA)") (class "Default")
      (node (ref "D9") (pin "A") (pinfunction "A_A") (pintype "passive"))
      (node (ref "R11") (pin "1") (pinfunction "1_1") (pintype "passive"))
    )
    (net (code "110") (name "Net-(D10-PadA)") (class "Default")
      (node (ref "D10") (pin "A") (pinfunction "A_A") (pintype "passive"))
      (node (ref "R12") (pin "1") (pinfunction "1_1") (pintype "passive"))
    )
    (net (code "111") (name "Net-(D11-PadA)") (class "Default")
      (node (ref "D11") (pin "A") (pinfunction "A_A") (pintype "passive"))
      (node (ref "R13") (pin "1") (pinfunction "1_1") (pintype "passive"))
    )
    (net (code "112") (name "Net-(D12-PadA)") (class "Default")
      (node (ref "D12") (pin "A") (pinfunction "A_A") (pintype "passive"))
      (node (ref "R14") (pin "1") (pinfunction "1_1") (pintype "passive"))
    )
    (net (code "113") (name "Net-(D14-PadA)") (class "Default")
      (node (ref "D14") (pin "A") (pinfunction "A_A") (pintype "passive"))
      (node (ref "RP9") (pin "8") (pinfunction "8_8") (pintype "passive"))
    )
    (net (code "114") (name "Net-(D15-A)") (class "Default")
      (node (ref "D15") (pin "1") (pinfunction "A_1") (pintype "passive"))
      (node (ref "F9") (pin "1") (pinfunction "1_1") (pintype "passive"))
    )
    (net (code "115") (name "Net-(D16-PadA)") (class "Default")
      (node (ref "D16") (pin "A") (pinfunction "A_A") (pintype "passive"))
      (node (ref "RP9") (pin "7") (pinfunction "7_7") (pintype "passive"))
    )
    (net (code "116") (name "Net-(D17-PadK)") (class "Default")
      (node (ref "D17") (pin "K") (pinfunction "K_K") (pintype "passive"))
      (node (ref "R40") (pin "2") (pinfunction "2_2") (pintype "passive"))
    )
    (net (code "117") (name "Net-(D18-PadK)") (class "Default")
      (node (ref "D18") (pin "K") (pinfunction "K_K") (pintype "passive"))
      (node (ref "R41") (pin "1") (pinfunction "1_1") (pintype "passive"))
    )
    (net (code "118") (name "Net-(D19-PadK)") (class "Default")
      (node (ref "D19") (pin "K") (pinfunction "K_K") (pintype "passive"))
      (node (ref "R42") (pin "1") (pinfunction "1_1") (pintype "passive"))
    )
    (net (code "119") (name "Net-(D20-PadK)") (class "Default")
      (node (ref "D20") (pin "K") (pinfunction "K_K") (pintype "passive"))
      (node (ref "R43") (pin "1") (pinfunction "1_1") (pintype "passive"))
    )
    (net (code "120") (name "Net-(D21-PadA)") (class "Default")
      (node (ref "D21") (pin "A") (pinfunction "A_A") (pintype "passive"))
      (node (ref "R44") (pin "1") (pinfunction "1_1") (pintype "passive"))
    )
    (net (code "121") (name "Net-(D22-PadA)") (class "Default")
      (node (ref "D22") (pin "A") (pinfunction "A_A") (pintype "passive"))
      (node (ref "RP9") (pin "5") (pinfunction "5_5") (pintype "passive"))
    )
    (net (code "122") (name "Net-(D23-PadA)") (class "Default")
      (node (ref "D23") (pin "A") (pinfunction "A_A") (pintype "passive"))
      (node (ref "RP9") (pin "6") (pinfunction "6_6") (pintype "passive"))
    )
    (net (code "123") (name "Net-(D24-K)") (class "Default")
      (node (ref "D24") (pin "2") (pinfunction "K_2") (pintype "passive"))
      (node (ref "F11") (pin "2") (pinfunction "2_2") (pintype "passive"))
    )
    (net (code "124") (name "Net-(D25-K)") (class "Default")
      (node (ref "D25") (pin "2") (pinfunction "K_2") (pintype "passive"))
      (node (ref "L2") (pin "1") (pinfunction "1_1") (pintype "passive"))
      (node (ref "U6") (pin "2") (pinfunction "OUT_2") (pintype "power_in"))
    )
    (net (code "125") (name "Net-(D26-K)") (class "Default")
      (node (ref "D26") (pin "2") (pinfunction "K_2") (pintype "passive"))
      (node (ref "F13") (pin "2") (pinfunction "2_2") (pintype "passive"))
    )
    (net (code "126") (name "Net-(F1-Pad1)") (class "Default")
      (node (ref "F1") (pin "1") (pinfunction "1_1") (pintype "passive"))
      (node (ref "REL2") (pin "3") (pintype "passive"))
    )
    (net (code "127") (name "Net-(F1-Pad2)") (class "Default")
      (node (ref "F1") (pin "2") (pinfunction "2_2") (pintype "passive"))
      (node (ref "J2") (pin "2") (pinfunction "2_2") (pintype "passive"))
    )
    (net (code "128") (name "Net-(F2-Pad1)") (class "Default")
      (node (ref "F2") (pin "1") (pinfunction "1_1") (pintype "passive"))
      (node (ref "REL3") (pin "3") (pintype "passive"))
    )
    (net (code "129") (name "Net-(F2-Pad2)") (class "Default")
      (node (ref "F2") (pin "2") (pinfunction "2_2") (pintype "passive"))
      (node (ref "J3") (pin "2") (pinfunction "2_2") (pintype "passive"))
    )
    (net (code "130") (name "Net-(F3-Pad1)") (class "Default")
      (node (ref "F3") (pin "1") (pinfunction "1_1") (pintype "passive"))
      (node (ref "REL4") (pin "3") (pintype "passive"))
    )
    (net (code "131") (name "Net-(F3-Pad2)") (class "Default")
      (node (ref "F3") (pin "2") (pinfunction "2_2") (pintype "passive"))
      (node (ref "J4") (pin "2") (pinfunction "2_2") (pintype "passive"))
    )
    (net (code "132") (name "Net-(F4-Pad1)") (class "Default")
      (node (ref "F4") (pin "1") (pinfunction "1_1") (pintype "passive"))
      (node (ref "REL5") (pin "3") (pintype "passive"))
    )
    (net (code "133") (name "Net-(F4-Pad2)") (class "Default")
      (node (ref "F4") (pin "2") (pinfunction "2_2") (pintype "passive"))
      (node (ref "J5") (pin "2") (pinfunction "2_2") (pintype "passive"))
    )
    (net (code "134") (name "Net-(F5-Pad1)") (class "Default")
      (node (ref "F5") (pin "1") (pinfunction "1_1") (pintype "passive"))
      (node (ref "REL6") (pin "3") (pintype "passive"))
    )
    (net (code "135") (name "Net-(F5-Pad2)") (class "Default")
      (node (ref "F5") (pin "2") (pinfunction "2_2") (pintype "passive"))
      (node (ref "J6") (pin "2") (pinfunction "2_2") (pintype "passive"))
    )
    (net (code "136") (name "Net-(F6-Pad1)") (class "Default")
      (node (ref "F6") (pin "1") (pinfunction "1_1") (pintype "passive"))
      (node (ref "REL7") (pin "3") (pintype "passive"))
    )
    (net (code "137") (name "Net-(F6-Pad2)") (class "Default")
      (node (ref "F6") (pin "2") (pinfunction "2_2") (pintype "passive"))
      (node (ref "J7") (pin "2") (pinfunction "2_2") (pintype "passive"))
    )
    (net (code "138") (name "Net-(F7-Pad1)") (class "Default")
      (node (ref "F7") (pin "1") (pinfunction "1_1") (pintype "passive"))
      (node (ref "REL1") (pin "3") (pintype "passive"))
    )
    (net (code "139") (name "Net-(F7-Pad2)") (class "Default")
      (node (ref "F7") (pin "2") (pinfunction "2_2") (pintype "passive"))
      (node (ref "J1") (pin "2") (pinfunction "2_2") (pintype "passive"))
    )
    (net (code "140") (name "Net-(F8-Pad1)") (class "Default")
      (node (ref "F8") (pin "1") (pinfunction "1_1") (pintype "passive"))
      (node (ref "P8") (pin "4") (pinfunction "4_4") (pintype "passive"))
    )
    (net (code "141") (name "Net-(F10-Pad2)") (class "Default")
      (node (ref "F10") (pin "2") (pinfunction "2_2") (pintype "passive"))
      (node (ref "L1") (pin "1") (pinfunction "A_1") (pintype "passive"))
    )
    (net (code "142") (name "Net-(LS1-B)") (class "Default")
      (node (ref "LS1") (pin "2") (pinfunction "B_2") (pintype "passive"))
      (node (ref "Q5") (pin "3") (pinfunction "C_3") (pintype "passive"))
    )
    (net (code "143") (name "Net-(P1-Pad2)") (class "Default")
      (node (ref "P1") (pin "2") (pinfunction "2_2") (pintype "passive"))
      (node (ref "RP3") (pin "4") (pinfunction "4_4") (pintype "passive"))
    )
    (net (code "144") (name "Net-(P1-Pad3)") (class "Default")
      (node (ref "P1") (pin "3") (pinfunction "3_3") (pintype "passive"))
      (node (ref "P2") (pin "3") (pinfunction "3_3") (pintype "passive"))
      (node (ref "P3") (pin "3") (pinfunction "3_3") (pintype "passive"))
      (node (ref "R21") (pin "2") (pinfunction "2_2") (pintype "passive"))
    )
    (net (code "145") (name "Net-(P2-Pad2)") (class "Default")
      (node (ref "P2") (pin "2") (pinfunction "2_2") (pintype "passive"))
      (node (ref "RP3") (pin "3") (pinfunction "3_3") (pintype "passive"))
    )
    (net (code "146") (name "Net-(P3-Pad2)") (class "Default")
      (node (ref "P3") (pin "2") (pinfunction "2_2") (pintype "passive"))
      (node (ref "RP3") (pin "1") (pinfunction "1_1") (pintype "passive"))
    )
    (net (code "147") (name "Net-(P4-Pad2)") (class "Default")
      (node (ref "P4") (pin "2") (pinfunction "2_2") (pintype "passive"))
      (node (ref "RP4") (pin "3") (pinfunction "3_3") (pintype "passive"))
    )
    (net (code "148") (name "Net-(P4-Pad3)") (class "Default")
      (node (ref "P4") (pin "3") (pinfunction "3_3") (pintype "passive"))
      (node (ref "RP4") (pin "2") (pinfunction "2_2") (pintype "passive"))
    )
    (net (code "149") (name "Net-(P4-Pad4)") (class "Default")
      (node (ref "P4") (pin "4") (pinfunction "4_4") (pintype "passive"))
      (node (ref "RP4") (pin "1") (pinfunction "1_1") (pintype "passive"))
    )
    (net (code "150") (name "Net-(P5-Pad2)") (class "Default")
      (node (ref "P5") (pin "2") (pinfunction "2_2") (pintype "passive"))
      (node (ref "RP5") (pin "3") (pinfunction "3_3") (pintype "passive"))
    )
    (net (code "151") (name "Net-(P5-Pad3)") (class "Default")
      (node (ref "P5") (pin "3") (pinfunction "3_3") (pintype "passive"))
      (node (ref "RP5") (pin "2") (pinfunction "2_2") (pintype "passive"))
    )
    (net (code "152") (name "Net-(P5-Pad4)") (class "Default")
      (node (ref "P5") (pin "4") (pinfunction "4_4") (pintype "passive"))
      (node (ref "RP5") (pin "1") (pinfunction "1_1") (pintype "passive"))
    )
    (net (code "153") (name "Net-(P6-Pad2)") (class "Default")
      (node (ref "P6") (pin "2") (pinfunction "2_2") (pintype "passive"))
      (node (ref "RP6") (pin "3") (pinfunction "3_3") (pintype "passive"))
    )
    (net (code "154") (name "Net-(P6-Pad3)") (class "Default")
      (node (ref "P6") (pin "3") (pinfunction "3_3") (pintype "passive"))
      (node (ref "RP6") (pin "2") (pinfunction "2_2") (pintype "passive"))
    )
    (net (code "155") (name "Net-(P6-Pad4)") (class "Default")
      (node (ref "P6") (pin "4") (pinfunction "4_4") (pintype "passive"))
      (node (ref "RP6") (pin "1") (pinfunction "1_1") (pintype "passive"))
    )
    (net (code "156") (name "Net-(P7-Pad12)") (class "Default")
      (node (ref "P7") (pin "12") (pinfunction "12_12") (pintype "passive"))
      (node (ref "R37") (pin "1") (pinfunction "1_1") (pintype "passive"))
    )
    (net (code "157") (name "Net-(P10-Pad5)") (class "Default")
      (node (ref "P10") (pin "5") (pinfunction "5_5") (pintype "passive"))
      (node (ref "R45") (pin "2") (pinfunction "2_2") (pintype "passive"))
    )
    (net (code "158") (name "Net-(P11-Pad5)") (class "Default")
      (node (ref "P11") (pin "5") (pinfunction "5_5") (pintype "passive"))
      (node (ref "R47") (pin "2") (pinfunction "2_2") (pintype "passive"))
    )
    (net (code "159") (name "Net-(P12-Pad5)") (class "Default")
      (node (ref "P12") (pin "5") (pinfunction "5_5") (pintype "passive"))
      (node (ref "R51") (pin "2") (pinfunction "2_2") (pintype "passive"))
    )
    (net (code "160") (name "Net-(Q1-B)") (class "Default")
      (node (ref "Q1") (pin "1") (pinfunction "B_1") (pintype "passive"))
      (node (ref "R4") (pin "1") (pinfunction "1_1") (pintype "passive"))
    )
    (net (code "161") (name "Net-(Q1-C)") (class "Default")
      (node (ref "D1") (pin "K") (pinfunction "K_K") (pintype "passive"))
      (node (ref "Q1") (pin "3") (pinfunction "C_3") (pintype "passive"))
    )
    (net (code "162") (name "Net-(Q2-B)") (class "Default")
      (node (ref "Q2") (pin "1") (pinfunction "B_1") (pintype "passive"))
      (node (ref "R1") (pin "1") (pinfunction "1_1") (pintype "passive"))
    )
    (net (code "163") (name "Net-(Q2-C)") (class "Default")
      (node (ref "D2") (pin "K") (pinfunction "K_K") (pintype "passive"))
      (node (ref "Q2") (pin "3") (pinfunction "C_3") (pintype "passive"))
    )
    (net (code "164") (name "Net-(Q3-B)") (class "Default")
      (node (ref "Q3") (pin "1") (pinfunction "B_1") (pintype "passive"))
      (node (ref "R2") (pin "1") (pinfunction "1_1") (pintype "passive"))
    )
    (net (code "165") (name "Net-(Q3-C)") (class "Default")
      (node (ref "D3") (pin "K") (pinfunction "K_K") (pintype "passive"))
      (node (ref "Q3") (pin "3") (pinfunction "C_3") (pintype "passive"))
    )
    (net (code "166") (name "Net-(Q4-B)") (class "Default")
      (node (ref "Q4") (pin "1") (pinfunction "B_1") (pintype "passive"))
      (node (ref "R3") (pin "1") (pinfunction "1_1") (pintype "passive"))
    )
    (net (code "167") (name "Net-(Q4-C)") (class "Default")
      (node (ref "D4") (pin "K") (pinfunction "K_K") (pintype "passive"))
      (node (ref "Q4") (pin "3") (pinfunction "C_3") (pintype "passive"))
    )
    (net (code "168") (name "Net-(Q5-B)") (class "Default")
      (node (ref "Q5") (pin "1") (pinfunction "B_1") (pintype "passive"))
      (node (ref "R36") (pin "1") (pinfunction "1_1") (pintype "passive"))
      (node (ref "R53") (pin "2") (pinfunction "2_2") (pintype "passive"))
    )
    (net (code "169") (name "Net-(U1-LINKA)") (class "Default")
      (node (ref "R1") (pin "2") (pinfunction "2_2") (pintype "passive"))
      (node (ref "U1") (pin "1") (pinfunction "LINKA_1") (pintype "passive"))
    )
    (net (code "170") (name "Net-(U1-LINKB)") (class "Default")
      (node (ref "R2") (pin "2") (pinfunction "2_2") (pintype "passive"))
      (node (ref "U1") (pin "2") (pinfunction "LINKB_2") (pintype "passive"))
    )
    (net (code "171") (name "Net-(U1-NET)") (class "Default")
      (node (ref "R4") (pin "2") (pinfunction "2_2") (pintype "passive"))
      (node (ref "U1") (pin "15") (pinfunction "NET_15") (pintype "passive"))
    )
    (net (code "172") (name "Net-(U1-WORK)") (class "Default")
      (node (ref "R3") (pin "2") (pinfunction "2_2") (pintype "passive"))
      (node (ref "U1") (pin "9") (pinfunction "WORK_9") (pintype "passive"))
    )
    (net (code "173") (name "Net-(U2A-PA15)") (class "Default")
      (node (ref "R16") (pin "2") (pinfunction "2_2") (pintype "passive"))
      (node (ref "U2") (pin "50") (pinfunction "PA15_50") (pintype "bidirectional"))
    )
    (net (code "174") (name "Net-(U6-VIN)") (class "Default")
      (node (ref "C19") (pin "1") (pinfunction "1_1") (pintype "passive"))
      (node (ref "C20") (pin "2") (pinfunction "2_2") (pintype "passive"))
      (node (ref "F12") (pin "1") (pinfunction "1_1") (pintype "passive"))
      (node (ref "U6") (pin "1") (pinfunction "VIN_1") (pintype "power_in"))
    )
    (net (code "175") (name "Net-(U7-Vin)") (class "Default")
      (node (ref "C17") (pin "1") (pinfunction "1_1") (pintype "passive"))
      (node (ref "C44") (pin "1") (pinfunction "1_1") (pintype "passive"))
      (node (ref "F11") (pin "1") (pinfunction "1_1") (pintype "passive"))
      (node (ref "U7") (pin "1") (pinfunction "Vin_1") (pintype "passive"))
    )
    (net (code "176") (name "Net-(VR1-Vin)") (class "Default")
      (node (ref "C39") (pin "1") (pinfunction "1_1") (pintype "passive"))
      (node (ref "C50") (pin "1") (pinfunction "1_1") (pintype "passive"))
      (node (ref "F13") (pin "1") (pinfunction "1_1") (pintype "passive"))
      (node (ref "VR1") (pin "3") (pinfunction "Vin_3") (pintype "passive"))
    )
    (net (code "177") (name "VCC3V3") (class "Default")
      (node (ref "C27") (pin "2") (pinfunction "2_2") (pintype "passive"))
      (node (ref "C28") (pin "2") (pinfunction "2_2") (pintype "passive"))
      (node (ref "C29") (pin "2") (pinfunction "2_2") (pintype "passive"))
      (node (ref "C30") (pin "2") (pinfunction "2_2") (pintype "passive"))
      (node (ref "C31") (pin "2") (pinfunction "2_2") (pintype "passive"))
      (node (ref "C32") (pin "2") (pinfunction "2_2") (pintype "passive"))
      (node (ref "C40") (pin "1") (pinfunction "1_1") (pintype "passive"))
      (node (ref "C41") (pin "1") (pinfunction "1_1") (pintype "passive"))
      (node (ref "C42") (pin "1") (pinfunction "1_1") (pintype "passive"))
      (node (ref "D1") (pin "A") (pinfunction "A_A") (pintype "passive"))
      (node (ref "D17") (pin "A") (pinfunction "A_A") (pintype "passive"))
      (node (ref "D2") (pin "A") (pinfunction "A_A") (pintype "passive"))
      (node (ref "D27") (pin "1") (pinfunction "A_1") (pintype "passive"))
      (node (ref "D3") (pin "A") (pinfunction "A_A") (pintype "passive"))
      (node (ref "D4") (pin "A") (pinfunction "A_A") (pintype "passive"))
      (node (ref "JP1") (pin "4") (pinfunction "4_4") (pintype "passive"))
      (node (ref "R35") (pin "2") (pinfunction "2_2") (pintype "passive"))
      (node (ref "R48") (pin "2") (pinfunction "2_2") (pintype "passive"))
      (node (ref "R49") (pin "2") (pinfunction "2_2") (pintype "passive"))
      (node (ref "RP7") (pin "5") (pinfunction "5_5") (pintype "passive"))
      (node (ref "RP7") (pin "6") (pinfunction "6_6") (pintype "passive"))
      (node (ref "RP7") (pin "7") (pinfunction "7_7") (pintype "passive"))
      (node (ref "RP7") (pin "8") (pinfunction "8_8") (pintype "passive"))
      (node (ref "RP8") (pin "5") (pinfunction "5_5") (pintype "passive"))
      (node (ref "RP8") (pin "6") (pinfunction "6_6") (pintype "passive"))
      (node (ref "RP8") (pin "7") (pinfunction "7_7") (pintype "passive"))
      (node (ref "RP8") (pin "8") (pinfunction "8_8") (pintype "passive"))
      (node (ref "RP9") (pin "1") (pinfunction "1_1") (pintype "passive"))
      (node (ref "RP9") (pin "2") (pinfunction "2_2") (pintype "passive"))
      (node (ref "RP9") (pin "3") (pinfunction "3_3") (pintype "passive"))
      (node (ref "RP9") (pin "4") (pinfunction "4_4") (pintype "passive"))
      (node (ref "U2") (pin "13") (pinfunction "VDDA_13") (pintype "power_in"))
      (node (ref "U2") (pin "19") (pinfunction "VDD_4_19") (pintype "power_in"))
      (node (ref "U2") (pin "32") (pinfunction "VDD_1_32") (pintype "power_in"))
      (node (ref "U2") (pin "48") (pinfunction "VDD_2_48") (pintype "power_in"))
      (node (ref "U2") (pin "64") (pinfunction "VDD_3_64") (pintype "power_in"))
      (node (ref "U4") (pin "11") (pinfunction "VDD_11") (pintype "passive"))
      (node (ref "U8") (pin "8") (pinfunction "VCC_8") (pintype "passive"))
      (node (ref "VR1") (pin "2") (pinfunction "Vout_2") (pintype "passive"))
    )
    (net (code "178") (name "VCC5V") (class "Default")
      (node (ref "C11") (pin "1") (pinfunction "1_1") (pintype "passive"))
      (node (ref "C21") (pin "1") (pinfunction "1_1") (pintype "passive"))
      (node (ref "C23") (pin "1") (pinfunction "1_1") (pintype "passive"))
      (node (ref "C24") (pin "2") (pinfunction "2_2") (pintype "passive"))
      (node (ref "C25") (pin "2") (pinfunction "2_2") (pintype "passive"))
      (node (ref "C35") (pin "2") (pinfunction "2_2") (pintype "passive"))
      (node (ref "C46") (pin "2") (pinfunction "2_2") (pintype "passive"))
      (node (ref "C47") (pin "2") (pinfunction "2_2") (pintype "passive"))
      (node (ref "C9") (pin "1") (pinfunction "1_1") (pintype "passive"))
      (node (ref "D18") (pin "A") (pinfunction "A_A") (pintype "passive"))
      (node (ref "D26") (pin "1") (pinfunction "A_1") (pintype "passive"))
      (node (ref "L2") (pin "2") (pinfunction "2_2") (pintype "passive"))
      (node (ref "LS1") (pin "1") (pinfunction "A_1") (pintype "passive"))
      (node (ref "P10") (pin "2") (pinfunction "2_2") (pintype "passive"))
      (node (ref "P10") (pin "4") (pinfunction "4_4") (pintype "passive"))
      (node (ref "P11") (pin "2") (pinfunction "2_2") (pintype "passive"))
      (node (ref "P11") (pin "4") (pinfunction "4_4") (pintype "passive"))
      (node (ref "P12") (pin "2") (pinfunction "2_2") (pintype "passive"))
      (node (ref "P12") (pin "4") (pinfunction "4_4") (pintype "passive"))
      (node (ref "P7") (pin "2") (pinfunction "2_2") (pintype "passive"))
      (node (ref "P9") (pin "1") (pinfunction "1_1") (pintype "passive"))
      (node (ref "R27") (pin "1") (pinfunction "1_1") (pintype "passive"))
      (node (ref "R28") (pin "1") (pinfunction "1_1") (pintype "passive"))
      (node (ref "R29") (pin "1") (pinfunction "1_1") (pintype "passive"))
      (node (ref "U6") (pin "4") (pinfunction "FB_4") (pintype "input"))
    )
    (net (code "179") (name "VCC12V") (class "Default")
      (node (ref "C1") (pin "1") (pinfunction "1_1") (pintype "passive"))
      (node (ref "C10") (pin "1") (pinfunction "1_1") (pintype "passive"))
      (node (ref "C45") (pin "1") (pinfunction "1_1") (pintype "passive"))
      (node (ref "C8") (pin "1") (pinfunction "1_1") (pintype "passive"))
      (node (ref "D24") (pin "1") (pinfunction "A_1") (pintype "passive"))
      (node (ref "F10") (pin "1") (pinfunction "1_1") (pintype "passive"))
      (node (ref "F12") (pin "2") (pinfunction "2_2") (pintype "passive"))
      (node (ref "F8") (pin "2") (pinfunction "2_2") (pintype "passive"))
      (node (ref "F9") (pin "2") (pinfunction "2_2") (pintype "passive"))
      (node (ref "NTC1") (pin "2") (pinfunction "2_2") (pintype "passive"))
      (node (ref "U1") (pin "13") (pinfunction "DC5-16V_13") (pintype "passive"))
      (node (ref "U1") (pin "14") (pinfunction "DC5-16V_14") (pintype "passive"))
    )
    (net (code "180") (name "VCC12VPUM") (class "Default")
      (node (ref "C13") (pin "1") (pinfunction "1_1") (pintype "passive"))
      (node (ref "C14") (pin "1") (pinfunction "1_1") (pintype "passive"))
      (node (ref "C15") (pin "1") (pinfunction "1_1") (pintype "passive"))
      (node (ref "D19") (pin "A") (pinfunction "A_A") (pintype "passive"))
      (node (ref "L1") (pin "2") (pinfunction "A_2") (pintype "passive"))
      (node (ref "REL1") (pin "2") (pintype "passive"))
      (node (ref "REL2") (pin "2") (pintype "passive"))
      (node (ref "REL3") (pin "2") (pintype "passive"))
      (node (ref "REL4") (pin "2") (pintype "passive"))
      (node (ref "REL5") (pin "2") (pintype "passive"))
      (node (ref "REL6") (pin "2") (pintype "passive"))
      (node (ref "REL7") (pin "2") (pintype "passive"))
    )
    (net (code "181") (name "VCC12VREL") (class "Default")
      (node (ref "C22") (pin "1") (pinfunction "1_1") (pintype "passive"))
      (node (ref "C4") (pin "1") (pinfunction "1_1") (pintype "passive"))
      (node (ref "C7") (pin "1") (pinfunction "1_1") (pintype "passive"))
      (node (ref "D15") (pin "2") (pinfunction "K_2") (pintype "passive"))
      (node (ref "R10") (pin "2") (pinfunction "2_2") (pintype "passive"))
      (node (ref "R11") (pin "2") (pinfunction "2_2") (pintype "passive"))
      (node (ref "R12") (pin "2") (pinfunction "2_2") (pintype "passive"))
      (node (ref "R13") (pin "2") (pinfunction "2_2") (pintype "passive"))
      (node (ref "R14") (pin "2") (pinfunction "2_2") (pintype "passive"))
      (node (ref "R5") (pin "2") (pinfunction "2_2") (pintype "passive"))
      (node (ref "R6") (pin "2") (pinfunction "2_2") (pintype "passive"))
      (node (ref "R7") (pin "2") (pinfunction "2_2") (pintype "passive"))
      (node (ref "REL1") (pin "5") (pintype "passive"))
      (node (ref "REL2") (pin "5") (pintype "passive"))
      (node (ref "REL3") (pin "5") (pintype "passive"))
      (node (ref "REL4") (pin "5") (pintype "passive"))
      (node (ref "REL5") (pin "5") (pintype "passive"))
      (node (ref "REL6") (pin "5") (pintype "passive"))
      (node (ref "REL7") (pin "5") (pintype "passive"))
      (node (ref "REL8") (pin "5") (pintype "passive"))
      (node (ref "U5") (pin "10") (pinfunction "COM_10") (pintype "passive"))
    )
    (net (code "182") (name "VCCP5V") (class "Default")
      (node (ref "C16") (pin "1") (pinfunction "1_1") (pintype "passive"))
      (node (ref "C18") (pin "1") (pinfunction "1_1") (pintype "passive"))
      (node (ref "C26") (pin "2") (pinfunction "2_2") (pintype "passive"))
      (node (ref "C43") (pin "2") (pinfunction "2_2") (pintype "passive"))
      (node (ref "D20") (pin "A") (pinfunction "A_A") (pintype "passive"))
      (node (ref "JP2") (pin "4") (pinfunction "4_4") (pintype "passive"))
      (node (ref "R30") (pin "1") (pinfunction "1_1") (pintype "passive"))
      (node (ref "R31") (pin "1") (pinfunction "1_1") (pintype "passive"))
      (node (ref "R32") (pin "1") (pinfunction "1_1") (pintype "passive"))
      (node (ref "R44") (pin "2") (pinfunction "2_2") (pintype "passive"))
      (node (ref "REL8") (pin "2") (pintype "passive"))
      (node (ref "U3") (pin "15") (pinfunction "VCC_15") (pintype "passive"))
      (node (ref "U7") (pin "3") (pinfunction "Vout_3") (pintype "passive"))
    )
    (net (code "183") (name "unconnected-(P8-Pad1)") (class "Default")
      (node (ref "P8") (pin "1") (pinfunction "1_1") (pintype "passive"))
    )
    (net (code "184") (name "unconnected-(P8-Pad3)") (class "Default")
      (node (ref "P8") (pin "3") (pinfunction "3_3") (pintype "passive"))
    )
    (net (code "185") (name "unconnected-(P10-Pad1)") (class "Default")
      (node (ref "P10") (pin "1") (pinfunction "1_1") (pintype "passive"))
    )
    (net (code "186") (name "unconnected-(P11-Pad1)") (class "Default")
      (node (ref "P11") (pin "1") (pinfunction "1_1") (pintype "passive"))
    )
    (net (code "187") (name "unconnected-(P12-Pad1)") (class "Default")
      (node (ref "P12") (pin "1") (pinfunction "1_1") (pintype "passive"))
    )
    (net (code "188") (name "unconnected-(RP3-Pad2)") (class "Default")
      (node (ref "RP3") (pin "2") (pinfunction "2_2") (pintype "passive"))
    )
    (net (code "189") (name "unconnected-(RP4-Pad4)") (class "Default")
      (node (ref "RP4") (pin "4") (pinfunction "4_4") (pintype "passive"))
    )
    (net (code "190") (name "unconnected-(RP4-Pad5)") (class "Default")
      (node (ref "RP4") (pin "5") (pinfunction "5_5") (pintype "passive"))
    )
    (net (code "191") (name "unconnected-(RP5-Pad4)") (class "Default")
      (node (ref "RP5") (pin "4") (pinfunction "4_4") (pintype "passive"))
    )
    (net (code "192") (name "unconnected-(RP5-Pad5)") (class "Default")
      (node (ref "RP5") (pin "5") (pinfunction "5_5") (pintype "passive"))
    )
    (net (code "193") (name "unconnected-(RP6-Pad4)") (class "Default")
      (node (ref "RP6") (pin "4") (pinfunction "4_4") (pintype "passive"))
    )
    (net (code "194") (name "unconnected-(RP6-Pad5)") (class "Default")
      (node (ref "RP6") (pin "5") (pinfunction "5_5") (pintype "passive"))
    )
    (net (code "195") (name "unconnected-(RP7-Pad4)") (class "Default")
      (node (ref "RP7") (pin "4") (pinfunction "4_4") (pintype "passive"))
    )
    (net (code "196") (name "unconnected-(U1-MIC_N-Pad21)") (class "Default")
      (node (ref "U1") (pin "21") (pinfunction "MIC_N_21") (pintype "passive"))
    )
    (net (code "197") (name "unconnected-(U1-MIC_P-Pad20)") (class "Default")
      (node (ref "U1") (pin "20") (pinfunction "MIC_P_20") (pintype "passive"))
    )
    (net (code "198") (name "unconnected-(U1-NC-Pad3)") (class "Default")
      (node (ref "U1") (pin "3") (pinfunction "NC_3") (pintype "passive"))
    )
    (net (code "199") (name "unconnected-(U1-NC-Pad4)") (class "Default")
      (node (ref "U1") (pin "4") (pinfunction "NC_4") (pintype "passive"))
    )
    (net (code "200") (name "unconnected-(U1-PWRKEY-Pad10)") (class "Default")
      (node (ref "U1") (pin "10") (pinfunction "PWRKEY_10") (pintype "passive"))
    )
    (net (code "201") (name "unconnected-(U1-RCV_N-Pad23)") (class "Default")
      (node (ref "U1") (pin "23") (pinfunction "RCV_N_23") (pintype "passive"))
    )
    (net (code "202") (name "unconnected-(U1-RCV_P-Pad22)") (class "Default")
      (node (ref "U1") (pin "22") (pinfunction "RCV_P_22") (pintype "passive"))
    )
    (net (code "203") (name "unconnected-(U1-RELOAD-Pad18)") (class "Default")
      (node (ref "U1") (pin "18") (pinfunction "RELOAD_18") (pintype "passive"))
    )
    (net (code "204") (name "unconnected-(U1-RESET-Pad19)") (class "Default")
      (node (ref "U1") (pin "19") (pinfunction "RESET_19") (pintype "passive"))
    )
    (net (code "205") (name "unconnected-(U1-RS485_EN-Pad17)") (class "Default")
      (node (ref "U1") (pin "17") (pinfunction "RS485_EN_17") (pintype "passive"))
    )
    (net (code "206") (name "unconnected-(U1-URXD2-Pad8)") (class "Default")
      (node (ref "U1") (pin "8") (pinfunction "URXD2_8") (pintype "passive"))
    )
    (net (code "207") (name "unconnected-(U1-UTXD2-Pad5)") (class "Default")
      (node (ref "U1") (pin "5") (pinfunction "UTXD2_5") (pintype "passive"))
    )
    (net (code "208") (name "unconnected-(U1-VCAP-Pad16)") (class "Default")
      (node (ref "U1") (pin "16") (pinfunction "VCAP_16") (pintype "passive"))
    )
    (net (code "209") (name "unconnected-(U2A-PA0-WKUP-Pad14)") (class "Default")
      (node (ref "U2") (pin "14") (pinfunction "PA0-WKUP_14") (pintype "bidirectional"))
    )
    (net (code "210") (name "unconnected-(U2A-PA1-Pad15)") (class "Default")
      (node (ref "U2") (pin "15") (pinfunction "PA1_15") (pintype "bidirectional"))
    )
    (net (code "211") (name "unconnected-(U2A-PA8-Pad41)") (class "Default")
      (node (ref "U2") (pin "41") (pinfunction "PA8_41") (pintype "bidirectional"))
    )
    (net (code "212") (name "unconnected-(U2A-PA11-Pad44)") (class "Default")
      (node (ref "U2") (pin "44") (pinfunction "PA11_44") (pintype "bidirectional"))
    )
    (net (code "213") (name "unconnected-(U2A-PA12-Pad45)") (class "Default")
      (node (ref "U2") (pin "45") (pinfunction "PA12_45") (pintype "bidirectional"))
    )
    (net (code "214") (name "unconnected-(U2A-PB3-Pad55)") (class "Default")
      (node (ref "U2") (pin "55") (pinfunction "PB3_55") (pintype "bidirectional"))
    )
    (net (code "215") (name "unconnected-(U2A-PB4-Pad56)") (class "Default")
      (node (ref "U2") (pin "56") (pinfunction "PB4_56") (pintype "bidirectional"))
    )
    (net (code "216") (name "unconnected-(U2A-PB5-Pad57)") (class "Default")
      (node (ref "U2") (pin "57") (pinfunction "PB5_57") (pintype "bidirectional"))
    )
    (net (code "217") (name "unconnected-(U2A-PB8-Pad61)") (class "Default")
      (node (ref "U2") (pin "61") (pinfunction "PB8_61") (pintype "bidirectional"))
    )
    (net (code "218") (name "unconnected-(U2A-PB9-Pad62)") (class "Default")
      (node (ref "U2") (pin "62") (pinfunction "PB9_62") (pintype "bidirectional"))
    )
    (net (code "219") (name "unconnected-(U2A-PB12-Pad33)") (class "Default")
      (node (ref "U2") (pin "33") (pinfunction "PB12_33") (pintype "bidirectional"))
    )
    (net (code "220") (name "unconnected-(U2A-PC6-Pad37)") (class "Default")
      (node (ref "U2") (pin "37") (pinfunction "PC6_37") (pintype "bidirectional"))
    )
    (net (code "221") (name "unconnected-(U2A-PC7-Pad38)") (class "Default")
      (node (ref "U2") (pin "38") (pinfunction "PC7_38") (pintype "bidirectional"))
    )
    (net (code "222") (name "unconnected-(U2A-PC8-Pad39)") (class "Default")
      (node (ref "U2") (pin "39") (pinfunction "PC8_39") (pintype "bidirectional"))
    )
    (net (code "223") (name "unconnected-(U2A-PC9-Pad40)") (class "Default")
      (node (ref "U2") (pin "40") (pinfunction "PC9_40") (pintype "bidirectional"))
    )
    (net (code "224") (name "unconnected-(U2A-PC13-TAMPER-RTC-Pad2)") (class "Default")
      (node (ref "U2") (pin "2") (pinfunction "PC13-TAMPER-RTC_2") (pintype "bidirectional"))
    )
    (net (code "225") (name "unconnected-(U3-P2.2{slash}A10{slash}MISO_2-Pad35)") (class "Default")
      (node (ref "U3") (pin "35") (pinfunction "P2.2/A10/MISO_2_35") (pintype "passive"))
    )
    (net (code "226") (name "unconnected-(U3-P2.3{slash}A11{slash}MOSI_2-Pad36)") (class "Default")
      (node (ref "U3") (pin "36") (pinfunction "P2.3/A11/MOSI_2_36") (pintype "passive"))
    )
    (net (code "227") (name "unconnected-(U3-P2.4{slash}A12{slash}ECI_3{slash}SS_2-Pad37)") (class "Default")
      (node (ref "U3") (pin "37") (pinfunction "P2.4/A12/ECI_3/SS_2_37") (pintype "passive"))
    )
    (net (code "228") (name "unconnected-(U3-P2.5{slash}A13{slash}CCP0_3-Pad38)") (class "Default")
      (node (ref "U3") (pin "38") (pinfunction "P2.5/A13/CCP0_3_38") (pintype "passive"))
    )
    (net (code "229") (name "unconnected-(U3-P2.6{slash}A14{slash}CCP1_3-Pad39)") (class "Default")
      (node (ref "U3") (pin "39") (pinfunction "P2.6/A14/CCP1_3_39") (pintype "passive"))
    )
    (net (code "230") (name "unconnected-(U3-P3.3{slash}INT1-Pad22)") (class "Default")
      (node (ref "U3") (pin "22") (pinfunction "P3.3/INT1_22") (pintype "passive+no_connect"))
    )
    (net (code "231") (name "unconnected-(U3-P3.4{slash}T0{slash}T1CLKO{slash}ECI_2-Pad23)") (class "Default")
      (node (ref "U3") (pin "23") (pinfunction "P3.4/T0/T1CLKO/ECI_2_23") (pintype "passive+no_connect"))
    )
    (net (code "232") (name "unconnected-(U3-P3.5{slash}T1{slash}T0CLKO{slash}CCP0_2-Pad26)") (class "Default")
      (node (ref "U3") (pin "26") (pinfunction "P3.5/T1/T0CLKO/CCP0_2_26") (pintype "passive+no_connect"))
    )
    (net (code "233") (name "unconnected-(U3-P4.0{slash}MOSI_3-Pad18)") (class "Default")
      (node (ref "U3") (pin "18") (pinfunction "P4.0/MOSI_3_18") (pintype "passive+no_connect"))
    )
    (net (code "234") (name "unconnected-(U3-P5.5{slash}CMP+-Pad16)") (class "Default")
      (node (ref "U3") (pin "16") (pinfunction "P5.5/CMP+_16") (pintype "passive+no_connect"))
    )
    (net (code "235") (name "unconnected-(U4-CTS-Pad3)") (class "Default")
      (node (ref "U4") (pin "3") (pinfunction "CTS_3") (pintype "passive"))
    )
    (net (code "236") (name "unconnected-(U4-ETH-Pad13)") (class "Default")
      (node (ref "U4") (pin "13") (pinfunction "ETH_13") (pintype "passive"))
    )
    (net (code "237") (name "unconnected-(U4-ETH-Pad14)") (class "Default")
      (node (ref "U4") (pin "14") (pinfunction "ETH_14") (pintype "passive"))
    )
    (net (code "238") (name "unconnected-(U4-LED_DATA-Pad7)") (class "Default")
      (node (ref "U4") (pin "7") (pinfunction "LED_DATA_7") (pintype "passive"))
    )
    (net (code "239") (name "unconnected-(U4-LED_LINK-Pad12)") (class "Default")
      (node (ref "U4") (pin "12") (pinfunction "LED_LINK_12") (pintype "passive"))
    )
    (net (code "240") (name "unconnected-(U4-NC-Pad1)") (class "Default")
      (node (ref "U4") (pin "1") (pinfunction "NC_1") (pintype "passive"))
    )
    (net (code "241") (name "unconnected-(U4-NC-Pad2)") (class "Default")
      (node (ref "U4") (pin "2") (pinfunction "NC_2") (pintype "passive"))
    )
    (net (code "242") (name "unconnected-(U4-RESET-Pad4)") (class "Default")
      (node (ref "U4") (pin "4") (pinfunction "RESET_4") (pintype "passive"))
    )
    (net (code "243") (name "unconnected-(U4-RST-Pad5)") (class "Default")
      (node (ref "U4") (pin "5") (pinfunction "RST_5") (pintype "passive"))
    )
    (net (code "244") (name "unconnected-(U4-Reload-Pad6)") (class "Default")
      (node (ref "U4") (pin "6") (pinfunction "Reload_6") (pintype "passive"))
    )
  )
)
